# EP4CE75.net
KiCad netlist of a schematic drawn in Altium Designer
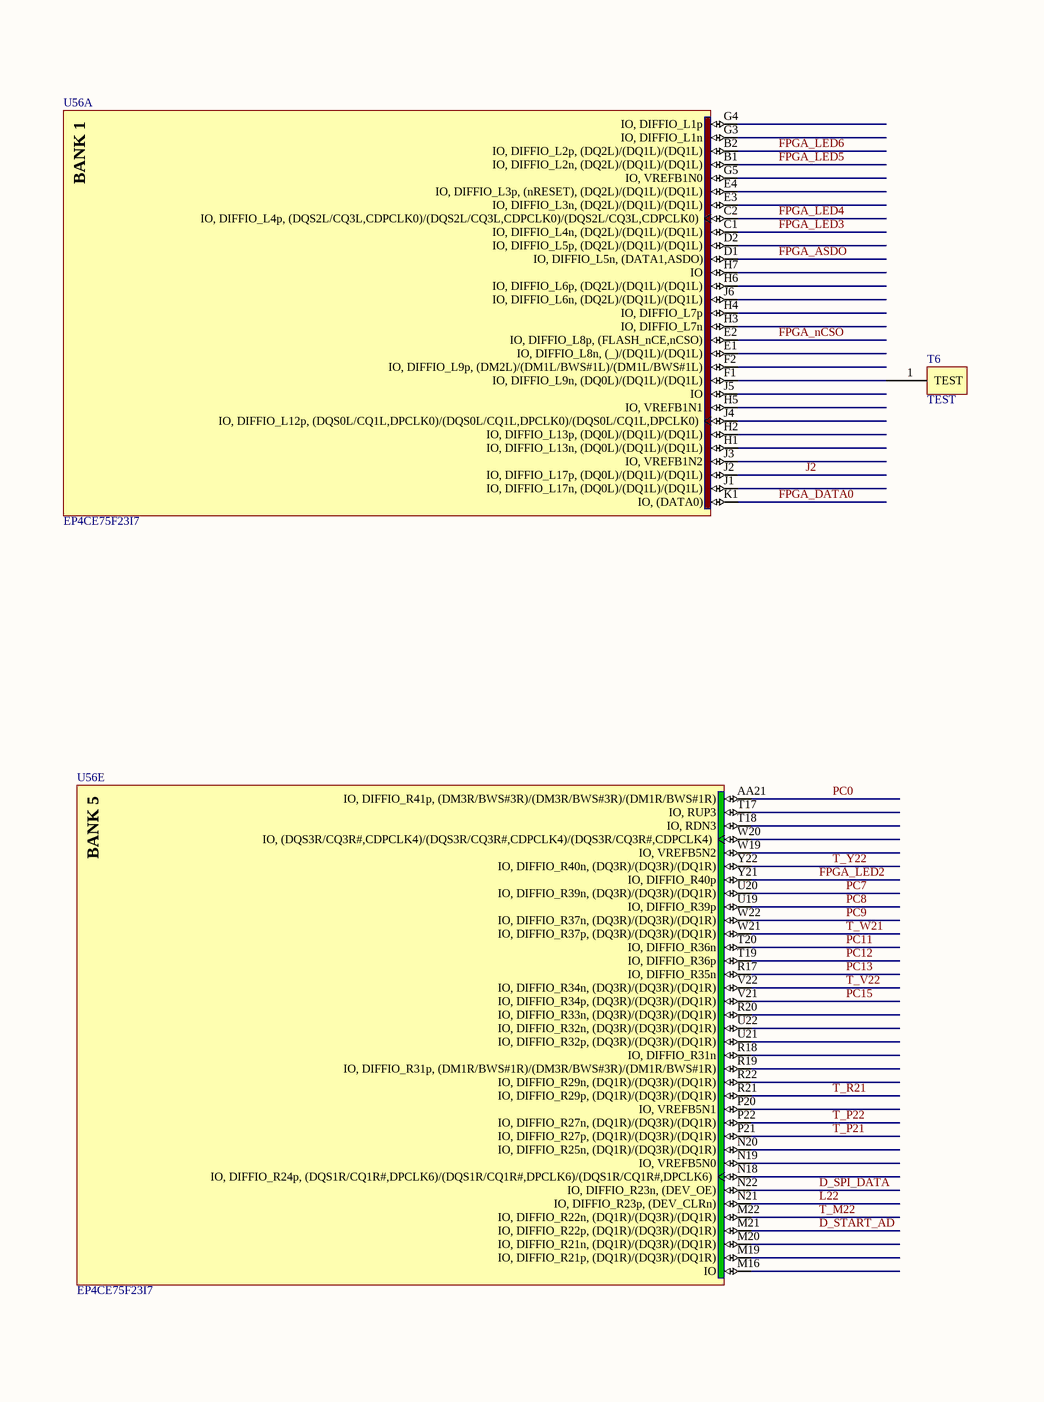
[diagram p0: EP4CE75.SchDoc, top left]
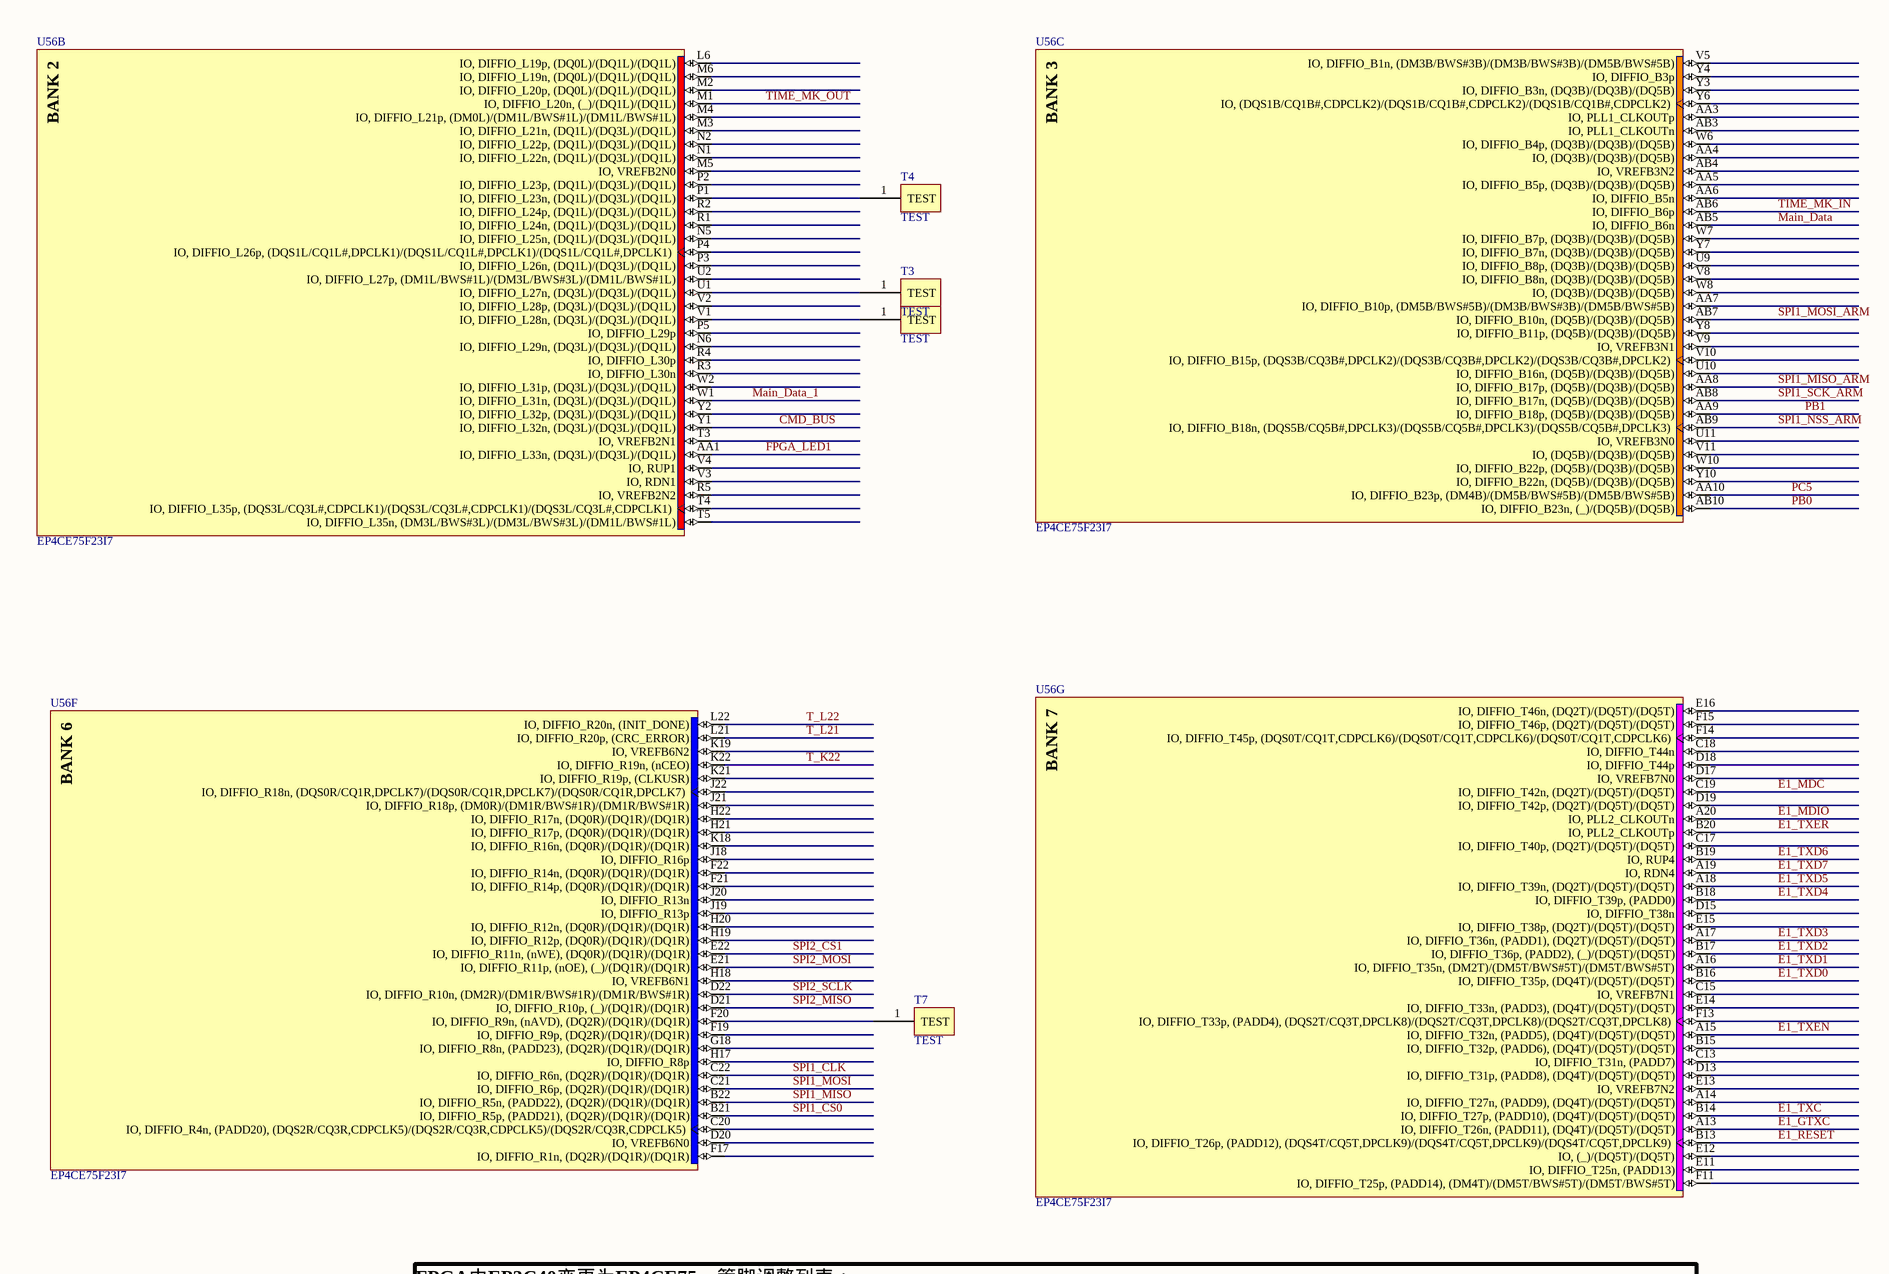
[diagram p1: EP4CE75.SchDoc, top middle]
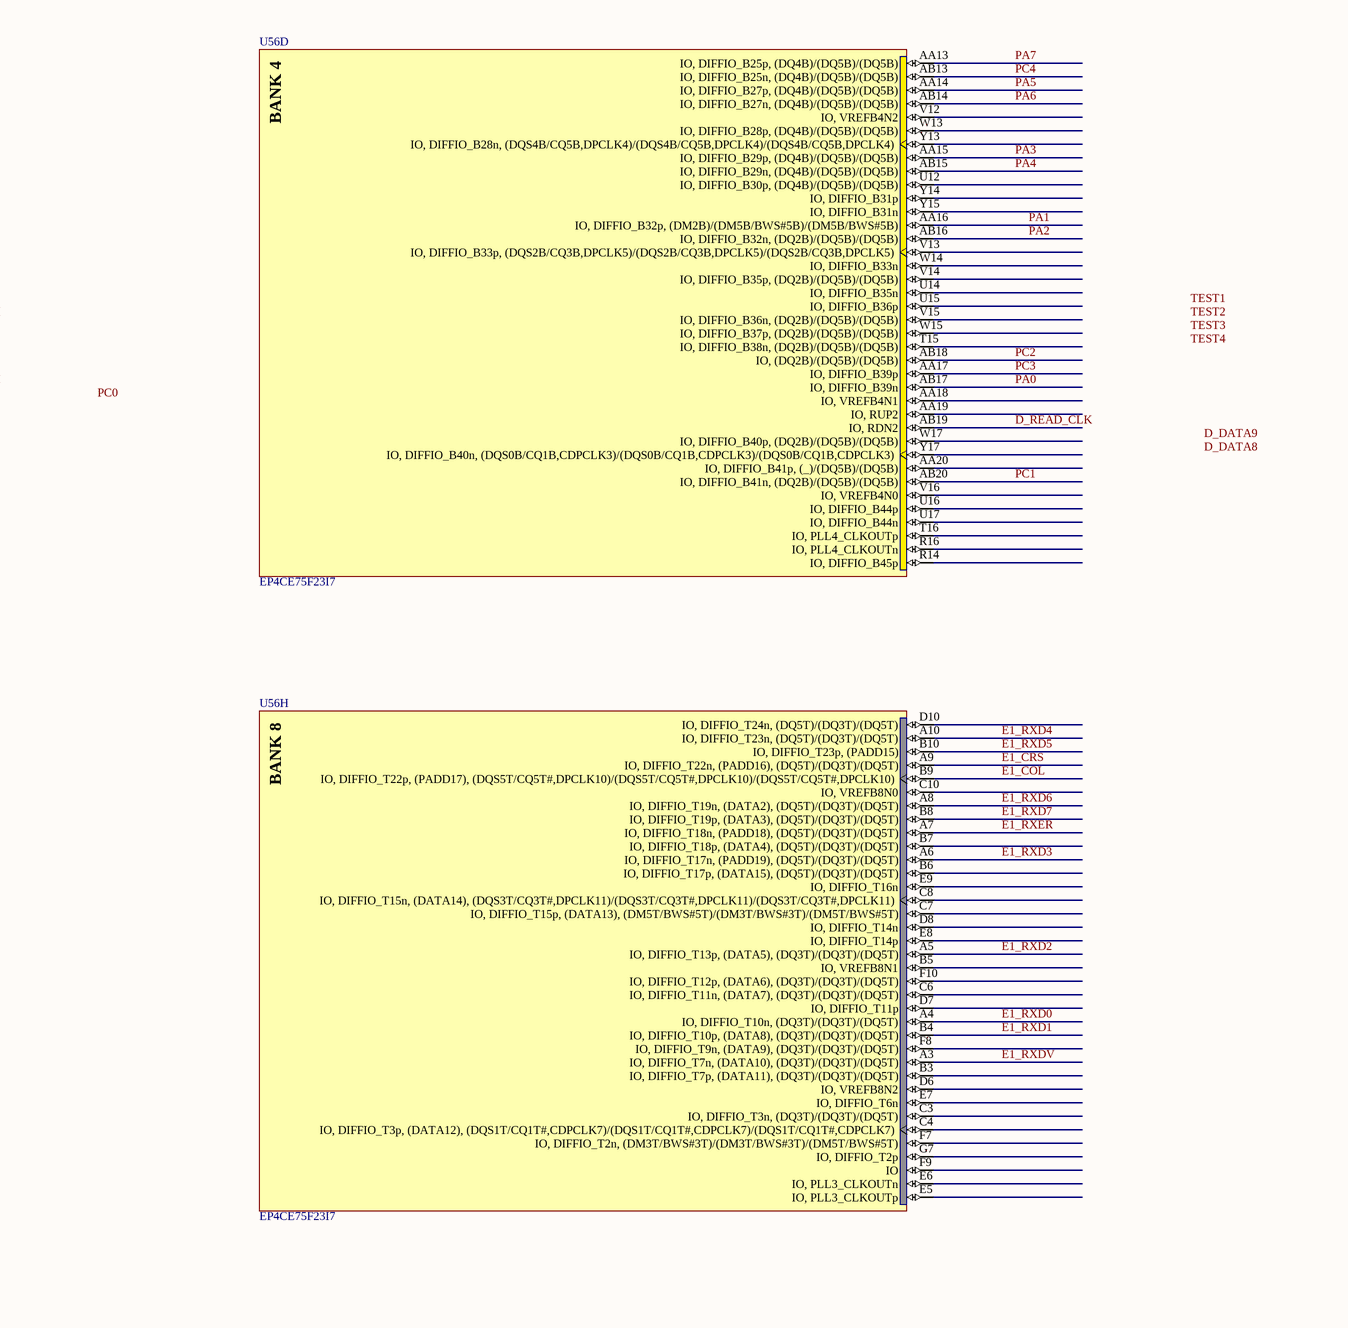
[diagram p2: EP4CE75.SchDoc, top right]
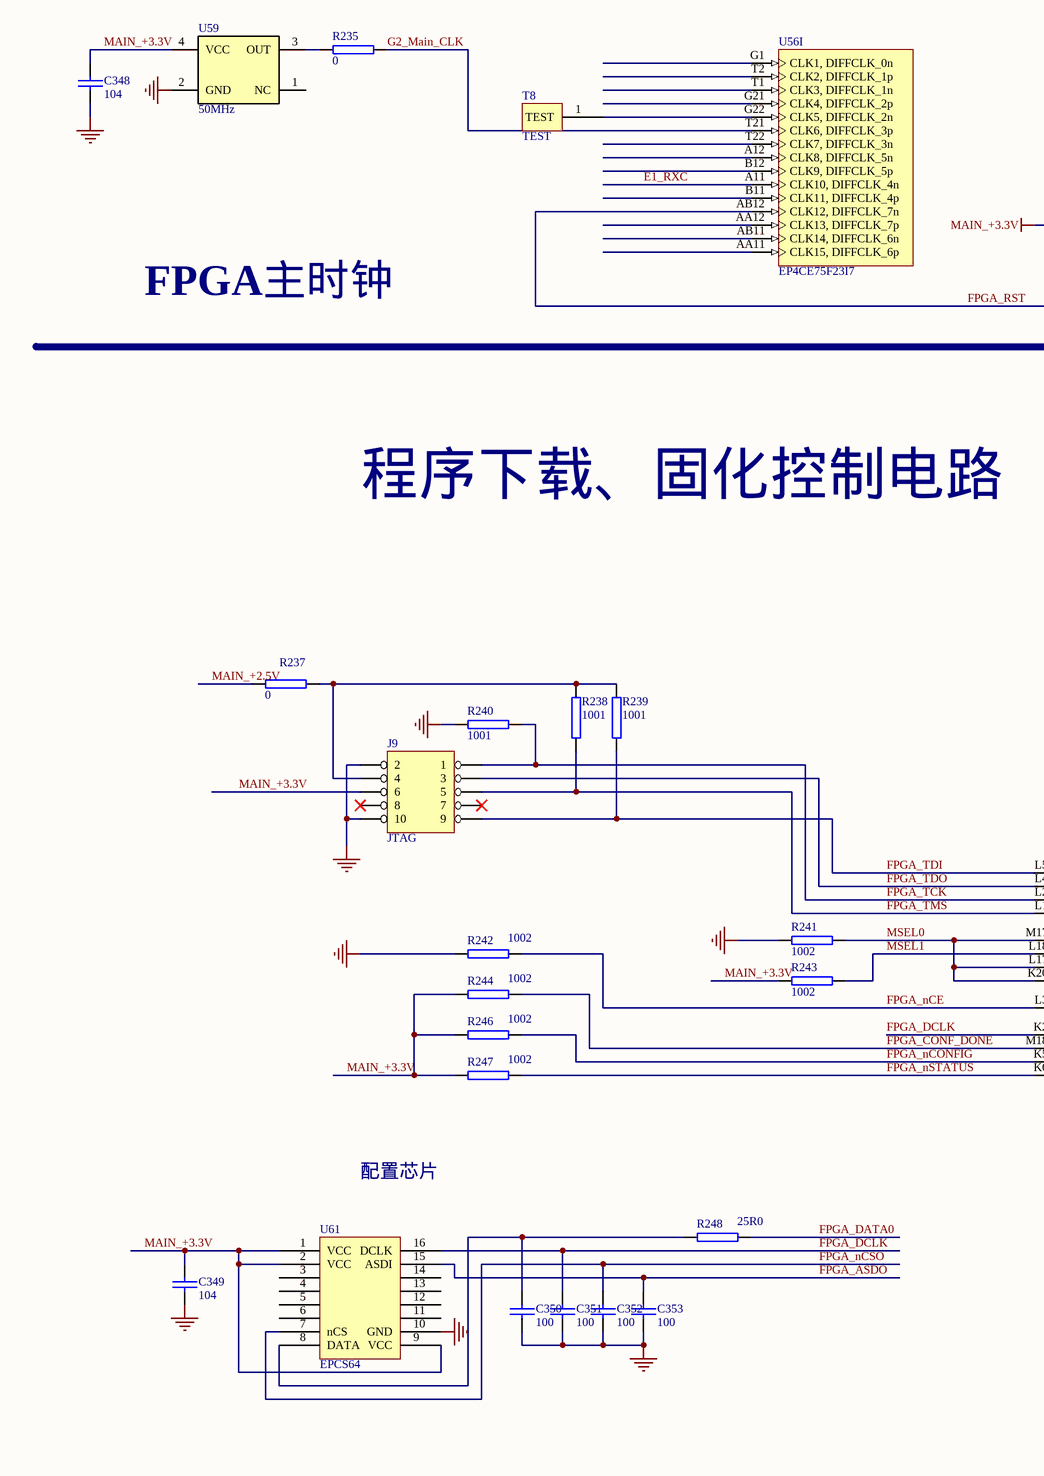
[diagram p3: EP4CE75.SchDoc, bottom left]
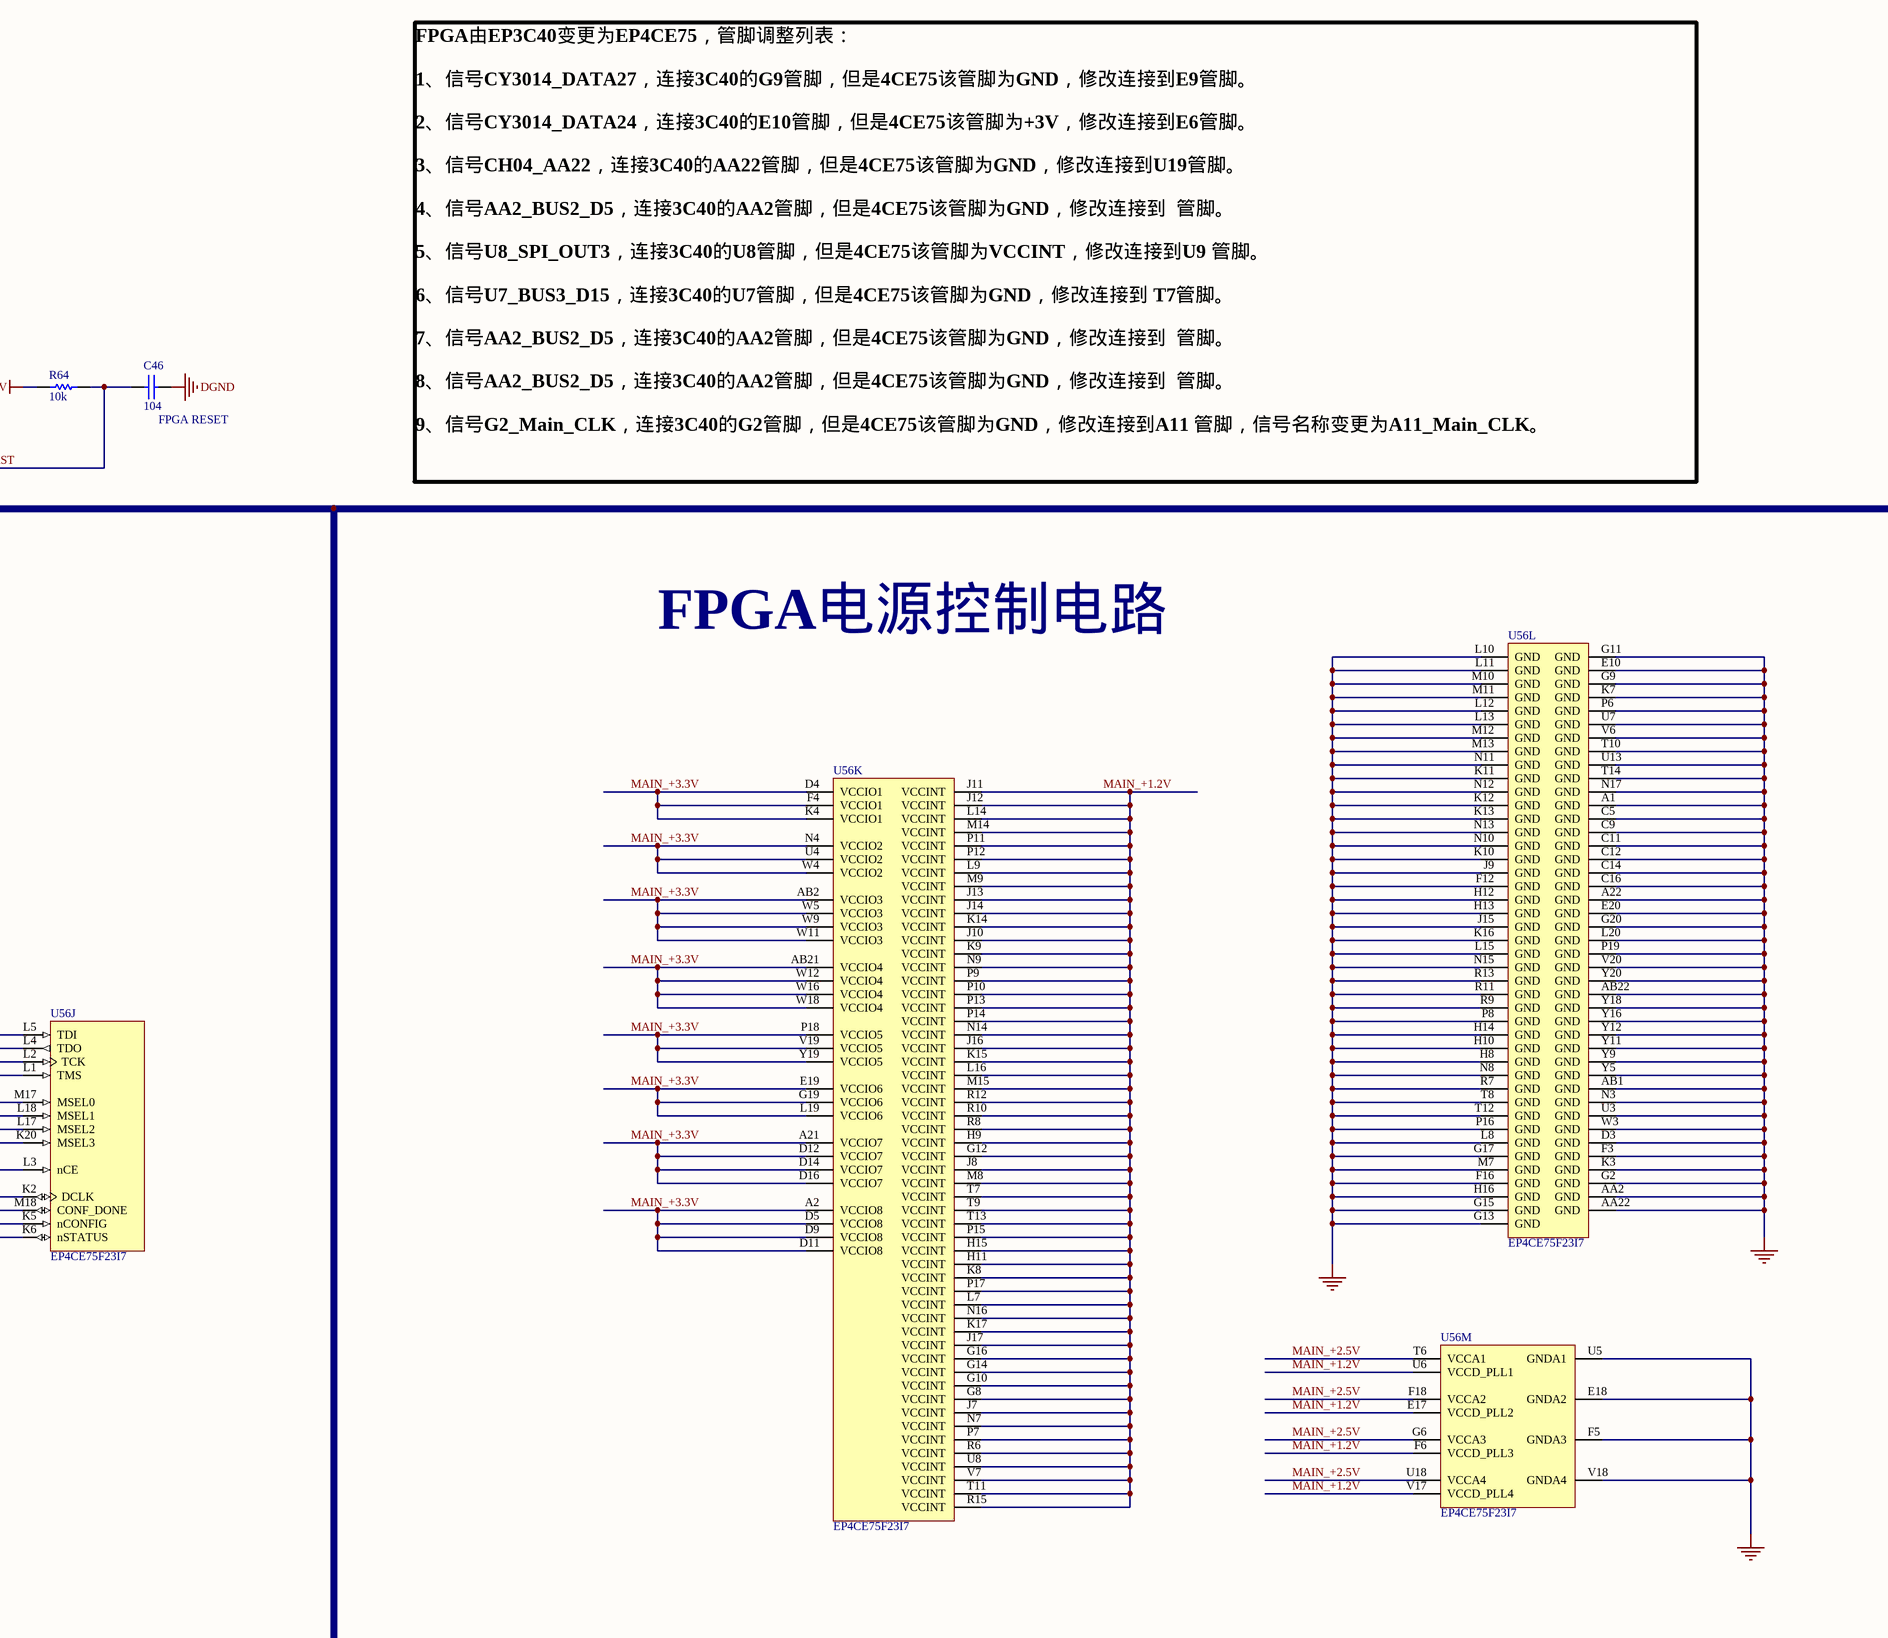
[diagram p4: EP4CE75.SchDoc, bottom middle]
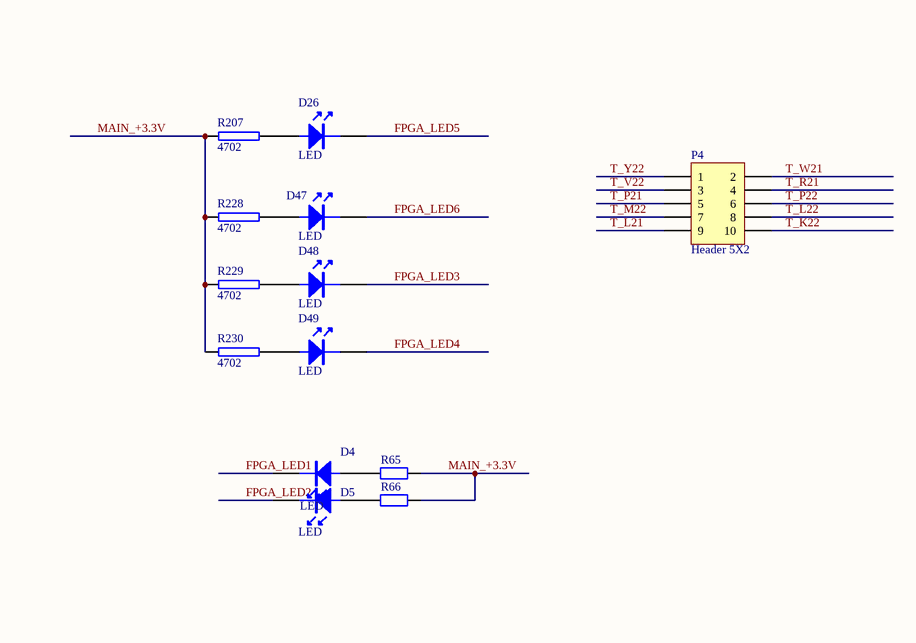
[diagram p5: EP4CE75.SchDoc, bottom right]

(export (version "E")
  (design (tool "Eeschema 10.0.6"))
  (components
    (comp (ref "C46")
      (value "104")
      (footprint "0805C")
      (description "Capacitor")
      (libsource (lib "*") (part "CAP"))
    )
    (comp (ref "C348")
      (value "104")
      (footprint "0805C")
      (description "Capacitor")
      (libsource (lib "") (part "CAP_1"))
    )
    (comp (ref "C349") (value "104") (footprint "0805C") (libsource (lib "*") (part "C")))
    (comp (ref "C350") (value "100") (footprint "0805C") (libsource (lib "*") (part "C")))
    (comp (ref "C351") (value "100") (footprint "0805C") (libsource (lib "*") (part "C")))
    (comp (ref "C352") (value "100") (footprint "0805C") (libsource (lib "*") (part "C")))
    (comp (ref "C353") (value "100") (footprint "0805C") (libsource (lib "*") (part "C")))
    (comp (ref "D4") (value "LED") (footprint "0805_LED") (libsource (lib "*") (part "LED")))
    (comp (ref "D5") (value "LED") (footprint "0805_LED") (libsource (lib "*") (part "LED")))
    (comp (ref "D26") (value "LED") (footprint "0805_LED") (libsource (lib "*") (part "LED")))
    (comp (ref "D47") (value "LED") (footprint "0805_LED") (libsource (lib "*") (part "LED")))
    (comp (ref "D48") (value "LED") (footprint "0805_LED") (libsource (lib "*") (part "LED")))
    (comp (ref "D49") (value "LED") (footprint "0805_LED") (libsource (lib "*") (part "LED")))
    (comp (ref "J9") (value "JTAG") (footprint "IDC10") (libsource (lib "*") (part "HEADER 5X2")))
    (comp (ref "P4")
      (value "Header 5X2")
      (footprint "HDR2X5")
      (description "Header, 5-Pin, Dual row")
      (fields (field (name "PUBLISHER") "Altium Limited"))
      (libsource (lib "Miscellaneous Connectors") (part "Header 5X2"))
    )
    (comp (ref "R64")
      (value "10k")
      (footprint "0805R")
      (description "Resistor")
      (fields (field (name "PUBLISHER") "*"))
      (libsource (lib "*") (part "res1"))
    )
    (comp (ref "R65")
      (value "4701")
      (footprint "0805R")
      (description "Resistor")
      (fields (field (name "PUBLISHER") "Altium Limited"))
      (libsource (lib "Miscellaneous Devices") (part "Res2"))
    )
    (comp (ref "R66")
      (value "4701")
      (footprint "0805R")
      (description "Resistor")
      (fields (field (name "PUBLISHER") "Altium Limited"))
      (libsource (lib "Miscellaneous Devices") (part "Res2"))
    )
    (comp (ref "R207") (value "4702") (footprint "0805R") (libsource (lib "*") (part "RES2")))
    (comp (ref "R228") (value "4702") (footprint "0805R") (libsource (lib "*") (part "RES2")))
    (comp (ref "R229") (value "4702") (footprint "0805R") (libsource (lib "*") (part "RES2")))
    (comp (ref "R230") (value "4702") (footprint "0805R") (libsource (lib "*") (part "RES2")))
    (comp (ref "R235") (value "0") (footprint "0805R") (libsource (lib "*") (part "RES2")))
    (comp (ref "R237") (value "0") (footprint "0805R") (libsource (lib "*") (part "RES2")))
    (comp (ref "R238") (value "1001") (footprint "0805R") (libsource (lib "*") (part "RES2")))
    (comp (ref "R239") (value "1001") (footprint "0805R") (libsource (lib "*") (part "RES2")))
    (comp (ref "R240") (value "1001") (footprint "0805R") (libsource (lib "*") (part "RES2")))
    (comp (ref "R241") (value "1002") (footprint "0805R") (libsource (lib "*") (part "RES2")))
    (comp (ref "R242") (value "1002") (footprint "0402") (libsource (lib "*") (part "RES2")))
    (comp (ref "R243") (value "1002") (footprint "0805R") (libsource (lib "*") (part "RES2")))
    (comp (ref "R244") (value "1002") (footprint "0402") (libsource (lib "*") (part "RES2")))
    (comp (ref "R246") (value "1002") (footprint "0402") (libsource (lib "*") (part "RES2")))
    (comp (ref "R247") (value "1002") (footprint "0402") (libsource (lib "*") (part "RES2")))
    (comp (ref "R248") (value "25R0") (footprint "0805R") (libsource (lib "*") (part "RES2")))
    (comp (ref "T3") (value "TEST") (footprint "TEST_MINI") (libsource (lib "") (part "TEST_1")))
    (comp (ref "T4") (value "TEST") (footprint "TEST_MINI") (libsource (lib "") (part "TEST_1")))
    (comp (ref "T5") (value "TEST") (footprint "TEST_MINI") (libsource (lib "") (part "TEST_1")))
    (comp (ref "T6") (value "TEST") (footprint "TEST_MINI") (libsource (lib "") (part "TEST_1")))
    (comp (ref "T7") (value "TEST") (footprint "TEST_MINI") (libsource (lib "") (part "TEST_1")))
    (comp (ref "T8") (value "TEST") (footprint "TEST_MINI") (libsource (lib "Schlib1") (part "TEST")))
    (comp (ref "U56")
      (value "EP4CE75F23I7")
      (footprint "FBGA484-3")
      (fields (field (name "PUBLISHER") "Altium Limited"))
      (libsource (lib "Altera Cyclone IV E") (part "EP4CE75F23I7"))
    )
    (comp (ref "U59") (value "50MHz") (footprint "CLOCK4") (libsource (lib "*") (part "OSC")))
    (comp (ref "U61")
      (value "EPCS64")
      (footprint "EPCS64_SOIC16")
      (libsource (lib "USB30_Project") (part "EPCS64"))
    )
  )
  (nets
    (net (code "1") (name "/CMD_BUS") (class "Default")
      (node (ref "U56") (pin "Y1") (pinfunction "IO,_DIFFIO_L32n,_(DQ3L)/(DQ3L)/(DQ1L)_Y1") (pintype "bidirectional"))
    )
    (net (code "4") (name "/D_READ_CLK") (class "Default")
      (node (ref "U56") (pin "AB19") (pinfunction "IO,_RDN2_AB19") (pintype "bidirectional"))
    )
    (net (code "5") (name "/D_SPI_DATA") (class "Default")
      (node (ref "U56") (pin "N22") (pinfunction "IO,_DIFFIO_R23n,_(DEV_OE)_N22") (pintype "bidirectional"))
    )
    (net (code "6") (name "/D_START_AD") (class "Default")
      (node (ref "U56") (pin "M21") (pinfunction "IO,_DIFFIO_R22p,_(DQ1R)/(DQ3R)/(DQ1R)_M21") (pintype "bidirectional"))
    )
    (net (code "7") (name "/E1_COL") (class "Default")
      (node (ref "U56") (pin "B9") (pinfunction "IO,_DIFFIO_T22p,_(PADD17),_(DQS5T/CQ5T#,DPCLK10)/(DQS5T/CQ5T#,DPCLK10)/(DQS5T/CQ5T#,DPCLK10)_B9") (pintype "bidirectional"))
    )
    (net (code "8") (name "/E1_CRS") (class "Default")
      (node (ref "U56") (pin "A9") (pinfunction "IO,_DIFFIO_T22n,_(PADD16),_(DQ5T)/(DQ3T)/(DQ5T)_A9") (pintype "bidirectional"))
    )
    (net (code "9") (name "/E1_GTXC") (class "Default")
      (node (ref "U56") (pin "A13") (pinfunction "IO,_DIFFIO_T26n,_(PADD11),_(DQ4T)/(DQ5T)/(DQ5T)_A13") (pintype "bidirectional"))
    )
    (net (code "10") (name "/E1_MDC") (class "Default")
      (node (ref "U56") (pin "C19") (pinfunction "IO,_DIFFIO_T42n,_(DQ2T)/(DQ5T)/(DQ5T)_C19") (pintype "bidirectional"))
    )
    (net (code "11") (name "/E1_MDIO") (class "Default")
      (node (ref "U56") (pin "A20") (pinfunction "IO,_PLL2_CLKOUTn_A20") (pintype "bidirectional"))
    )
    (net (code "12") (name "/E1_RESET") (class "Default")
      (node (ref "U56") (pin "B13") (pinfunction "IO,_DIFFIO_T26p,_(PADD12),_(DQS4T/CQ5T,DPCLK9)/(DQS4T/CQ5T,DPCLK9)/(DQS4T/CQ5T,DPCLK9)_B13") (pintype "bidirectional"))
    )
    (net (code "13") (name "/E1_RXC") (class "Default")
      (node (ref "U56") (pin "A11") (pinfunction "CLK10,_DIFFCLK_4n_A11") (pintype "input"))
    )
    (net (code "14") (name "/E1_RXD0") (class "Default")
      (node (ref "U56") (pin "A4") (pinfunction "IO,_DIFFIO_T10n,_(DQ3T)/(DQ3T)/(DQ5T)_A4") (pintype "bidirectional"))
    )
    (net (code "15") (name "/E1_RXD1") (class "Default")
      (node (ref "U56") (pin "B4") (pinfunction "IO,_DIFFIO_T10p,_(DATA8),_(DQ3T)/(DQ3T)/(DQ5T)_B4") (pintype "bidirectional"))
    )
    (net (code "16") (name "/E1_RXD2") (class "Default")
      (node (ref "U56") (pin "A5") (pinfunction "IO,_DIFFIO_T13p,_(DATA5),_(DQ3T)/(DQ3T)/(DQ5T)_A5") (pintype "bidirectional"))
    )
    (net (code "17") (name "/E1_RXD3") (class "Default")
      (node (ref "U56") (pin "A6") (pinfunction "IO,_DIFFIO_T17n,_(PADD19),_(DQ5T)/(DQ3T)/(DQ5T)_A6") (pintype "bidirectional"))
    )
    (net (code "18") (name "/E1_RXD4") (class "Default")
      (node (ref "U56") (pin "A10") (pinfunction "IO,_DIFFIO_T23n,_(DQ5T)/(DQ3T)/(DQ5T)_A10") (pintype "bidirectional"))
    )
    (net (code "19") (name "/E1_RXD5") (class "Default")
      (node (ref "U56") (pin "B10") (pinfunction "IO,_DIFFIO_T23p,_(PADD15)_B10") (pintype "bidirectional"))
    )
    (net (code "20") (name "/E1_RXD6") (class "Default")
      (node (ref "U56") (pin "A8") (pinfunction "IO,_DIFFIO_T19n,_(DATA2),_(DQ5T)/(DQ3T)/(DQ5T)_A8") (pintype "bidirectional"))
    )
    (net (code "21") (name "/E1_RXD7") (class "Default")
      (node (ref "U56") (pin "B8") (pinfunction "IO,_DIFFIO_T19p,_(DATA3),_(DQ5T)/(DQ3T)/(DQ5T)_B8") (pintype "bidirectional"))
    )
    (net (code "22") (name "/E1_RXDV") (class "Default")
      (node (ref "U56") (pin "A3") (pinfunction "IO,_DIFFIO_T7n,_(DATA10),_(DQ3T)/(DQ3T)/(DQ5T)_A3") (pintype "bidirectional"))
    )
    (net (code "23") (name "/E1_RXER") (class "Default")
      (node (ref "U56") (pin "A7") (pinfunction "IO,_DIFFIO_T18n,_(PADD18),_(DQ5T)/(DQ3T)/(DQ5T)_A7") (pintype "bidirectional"))
    )
    (net (code "24") (name "/E1_TXC") (class "Default")
      (node (ref "U56") (pin "B14") (pinfunction "IO,_DIFFIO_T27p,_(PADD10),_(DQ4T)/(DQ5T)/(DQ5T)_B14") (pintype "bidirectional"))
    )
    (net (code "25") (name "/E1_TXD0") (class "Default")
      (node (ref "U56") (pin "B16") (pinfunction "IO,_DIFFIO_T35p,_(DQ4T)/(DQ5T)/(DQ5T)_B16") (pintype "bidirectional"))
    )
    (net (code "26") (name "/E1_TXD1") (class "Default")
      (node (ref "U56") (pin "A16") (pinfunction "IO,_DIFFIO_T35n,_(DM2T)/(DM5T/BWS#5T)/(DM5T/BWS#5T)_A16") (pintype "bidirectional"))
    )
    (net (code "27") (name "/E1_TXD2") (class "Default")
      (node (ref "U56") (pin "B17") (pinfunction "IO,_DIFFIO_T36p,_(PADD2),_(_)/(DQ5T)/(DQ5T)_B17") (pintype "bidirectional"))
    )
    (net (code "28") (name "/E1_TXD3") (class "Default")
      (node (ref "U56") (pin "A17") (pinfunction "IO,_DIFFIO_T36n,_(PADD1),_(DQ2T)/(DQ5T)/(DQ5T)_A17") (pintype "bidirectional"))
    )
    (net (code "29") (name "/E1_TXD4") (class "Default")
      (node (ref "U56") (pin "B18") (pinfunction "IO,_DIFFIO_T39p,_(PADD0)_B18") (pintype "bidirectional"))
    )
    (net (code "30") (name "/E1_TXD5") (class "Default")
      (node (ref "U56") (pin "A18") (pinfunction "IO,_DIFFIO_T39n,_(DQ2T)/(DQ5T)/(DQ5T)_A18") (pintype "bidirectional"))
    )
    (net (code "31") (name "/E1_TXD6") (class "Default")
      (node (ref "U56") (pin "B19") (pinfunction "IO,_RUP4_B19") (pintype "bidirectional"))
    )
    (net (code "32") (name "/E1_TXD7") (class "Default")
      (node (ref "U56") (pin "A19") (pinfunction "IO,_RDN4_A19") (pintype "bidirectional"))
    )
    (net (code "33") (name "/E1_TXEN") (class "Default")
      (node (ref "U56") (pin "A15") (pinfunction "IO,_DIFFIO_T32n,_(PADD5),_(DQ4T)/(DQ5T)/(DQ5T)_A15") (pintype "bidirectional"))
    )
    (net (code "34") (name "/E1_TXER") (class "Default")
      (node (ref "U56") (pin "B20") (pinfunction "IO,_PLL2_CLKOUTp_B20") (pintype "bidirectional"))
    )
    (net (code "35") (name "/FPGA_ASDO") (class "Default")
      (node (ref "C353") (pin "2") (pintype "passive"))
      (node (ref "U56") (pin "D1") (pinfunction "IO,_DIFFIO_L5n,_(DATA1,ASDO)_D1") (pintype "bidirectional"))
      (node (ref "U61") (pin "15") (pinfunction "ASDI_15") (pintype "passive"))
    )
    (net (code "36") (name "/FPGA_CONF_DONE") (class "Default")
      (node (ref "R244") (pin "2") (pinfunction "2_2") (pintype "passive"))
      (node (ref "U56") (pin "M18") (pinfunction "CONF_DONE_M18") (pintype "bidirectional"))
    )
    (net (code "37") (name "/FPGA_DATA0") (class "Default")
      (node (ref "R248") (pin "1") (pinfunction "1_1") (pintype "passive"))
      (node (ref "U56") (pin "K1") (pinfunction "IO,_(DATA0)_K1") (pintype "bidirectional"))
    )
    (net (code "38") (name "/FPGA_DCLK") (class "Default")
      (node (ref "C351") (pin "2") (pintype "passive"))
      (node (ref "U56") (pin "K2") (pinfunction "DCLK_K2") (pintype "bidirectional"))
      (node (ref "U61") (pin "16") (pinfunction "DCLK_16") (pintype "passive"))
    )
    (net (code "39") (name "/FPGA_LED1") (class "Default")
      (node (ref "D4") (pin "2") (pinfunction "K_2") (pintype "passive"))
      (node (ref "U56") (pin "AA1") (pinfunction "IO,_DIFFIO_L33n,_(DQ3L)/(DQ3L)/(DQ1L)_AA1") (pintype "bidirectional"))
    )
    (net (code "40") (name "/FPGA_LED2") (class "Default")
      (node (ref "D5") (pin "2") (pinfunction "K_2") (pintype "passive"))
      (node (ref "U56") (pin "Y21") (pinfunction "IO,_DIFFIO_R40p_Y21") (pintype "bidirectional"))
    )
    (net (code "41") (name "/FPGA_LED3") (class "Default")
      (node (ref "D48") (pin "2") (pinfunction "K_2") (pintype "passive"))
      (node (ref "U56") (pin "C1") (pinfunction "IO,_DIFFIO_L4n,_(DQ2L)/(DQ1L)/(DQ1L)_C1") (pintype "bidirectional"))
    )
    (net (code "42") (name "/FPGA_LED4") (class "Default")
      (node (ref "D49") (pin "2") (pinfunction "K_2") (pintype "passive"))
      (node (ref "U56") (pin "C2") (pinfunction "IO,_DIFFIO_L4p,_(DQS2L/CQ3L,CDPCLK0)/(DQS2L/CQ3L,CDPCLK0)/(DQS2L/CQ3L,CDPCLK0)_C2") (pintype "bidirectional"))
    )
    (net (code "43") (name "/FPGA_LED5") (class "Default")
      (node (ref "D26") (pin "2") (pinfunction "K_2") (pintype "passive"))
      (node (ref "U56") (pin "B1") (pinfunction "IO,_DIFFIO_L2n,_(DQ2L)/(DQ1L)/(DQ1L)_B1") (pintype "bidirectional"))
    )
    (net (code "44") (name "/FPGA_LED6") (class "Default")
      (node (ref "D47") (pin "2") (pinfunction "K_2") (pintype "passive"))
      (node (ref "U56") (pin "B2") (pinfunction "IO,_DIFFIO_L2p,_(DQ2L)/(DQ1L)/(DQ1L)_B2") (pintype "bidirectional"))
    )
    (net (code "45") (name "/FPGA_RST") (class "Default")
      (node (ref "C46") (pin "1") (pinfunction "1_1") (pintype "passive"))
      (node (ref "R64") (pin "1") (pinfunction "1_1") (pintype "passive"))
      (node (ref "U56") (pin "AB12") (pinfunction "CLK12,_DIFFCLK_7n_AB12") (pintype "input"))
    )
    (net (code "46") (name "/FPGA_TCK") (class "Default")
      (node (ref "J9") (pin "1") (pinfunction "1_1") (pintype "passive"))
      (node (ref "R240") (pin "2") (pinfunction "2_2") (pintype "passive"))
      (node (ref "U56") (pin "L2") (pinfunction "TCK_L2") (pintype "input"))
    )
    (net (code "47") (name "/FPGA_TDI") (class "Default")
      (node (ref "J9") (pin "9") (pinfunction "9_9") (pintype "passive"))
      (node (ref "R239") (pin "1") (pinfunction "1_1") (pintype "passive"))
      (node (ref "U56") (pin "L5") (pinfunction "TDI_L5") (pintype "input"))
    )
    (net (code "48") (name "/FPGA_TDO") (class "Default")
      (node (ref "J9") (pin "3") (pinfunction "3_3") (pintype "passive"))
      (node (ref "U56") (pin "L4") (pinfunction "TDO_L4") (pintype "output"))
    )
    (net (code "49") (name "/FPGA_TMS") (class "Default")
      (node (ref "J9") (pin "5") (pinfunction "5_5") (pintype "passive"))
      (node (ref "R238") (pin "1") (pinfunction "1_1") (pintype "passive"))
      (node (ref "U56") (pin "L1") (pinfunction "TMS_L1") (pintype "input"))
    )
    (net (code "50") (name "/FPGA_nCE") (class "Default")
      (node (ref "R242") (pin "1") (pinfunction "1_1") (pintype "passive"))
      (node (ref "U56") (pin "L3") (pinfunction "nCE_L3") (pintype "input"))
    )
    (net (code "51") (name "/FPGA_nCONFIG") (class "Default")
      (node (ref "R246") (pin "1") (pinfunction "1_1") (pintype "passive"))
      (node (ref "U56") (pin "K5") (pinfunction "nCONFIG_K5") (pintype "input"))
    )
    (net (code "52") (name "/FPGA_nCSO") (class "Default")
      (node (ref "C352") (pin "2") (pintype "passive"))
      (node (ref "U56") (pin "E2") (pinfunction "IO,_DIFFIO_L8p,_(FLASH_nCE,nCSO)_E2") (pintype "bidirectional"))
      (node (ref "U61") (pin "7") (pinfunction "nCS_7") (pintype "passive"))
    )
    (net (code "53") (name "/FPGA_nSTATUS") (class "Default")
      (node (ref "R247") (pin "1") (pinfunction "1_1") (pintype "passive"))
      (node (ref "U56") (pin "K6") (pinfunction "nSTATUS_K6") (pintype "bidirectional"))
    )
    (net (code "54") (name "/G2_Main_CLK") (class "Default")
      (node (ref "R235") (pin "2") (pinfunction "2_2") (pintype "passive"))
      (node (ref "U56") (pin "T21") (pinfunction "CLK6,_DIFFCLK_3p_T21") (pintype "input"))
    )
    (net (code "55") (name "/J2") (class "Default")
      (node (ref "U56") (pin "J2") (pinfunction "IO,_DIFFIO_L17p,_(DQ0L)/(DQ1L)/(DQ1L)_J2") (pintype "bidirectional"))
    )
    (net (code "56") (name "/L22") (class "Default")
      (node (ref "U56") (pin "N21") (pinfunction "IO,_DIFFIO_R23p,_(DEV_CLRn)_N21") (pintype "bidirectional"))
    )
    (net (code "57") (name "/MAIN_+1.2V") (class "Default")
      (node (ref "U56") (pin "E17") (pinfunction "VCCD_PLL2_E17") (pintype "power_in"))
      (node (ref "U56") (pin "F6") (pinfunction "VCCD_PLL3_F6") (pintype "power_in"))
      (node (ref "U56") (pin "G10") (pinfunction "VCCINT_G10") (pintype "power_in"))
      (node (ref "U56") (pin "G12") (pinfunction "VCCINT_G12") (pintype "power_in"))
      (node (ref "U56") (pin "G14") (pinfunction "VCCINT_G14") (pintype "power_in"))
      (node (ref "U56") (pin "G16") (pinfunction "VCCINT_G16") (pintype "power_in"))
      (node (ref "U56") (pin "G8") (pinfunction "VCCINT_G8") (pintype "power_in"))
      (node (ref "U56") (pin "H11") (pinfunction "VCCINT_H11") (pintype "power_in"))
      (node (ref "U56") (pin "H15") (pinfunction "VCCINT_H15") (pintype "power_in"))
      (node (ref "U56") (pin "H9") (pinfunction "VCCINT_H9") (pintype "power_in"))
      (node (ref "U56") (pin "J10") (pinfunction "VCCINT_J10") (pintype "power_in"))
      (node (ref "U56") (pin "J11") (pinfunction "VCCINT_J11") (pintype "power_in"))
      (node (ref "U56") (pin "J12") (pinfunction "VCCINT_J12") (pintype "power_in"))
      (node (ref "U56") (pin "J13") (pinfunction "VCCINT_J13") (pintype "power_in"))
      (node (ref "U56") (pin "J14") (pinfunction "VCCINT_J14") (pintype "power_in"))
      (node (ref "U56") (pin "J16") (pinfunction "VCCINT_J16") (pintype "power_in"))
      (node (ref "U56") (pin "J17") (pinfunction "VCCINT_J17") (pintype "power_in"))
      (node (ref "U56") (pin "J7") (pinfunction "VCCINT_J7") (pintype "power_in"))
      (node (ref "U56") (pin "J8") (pinfunction "VCCINT_J8") (pintype "power_in"))
      (node (ref "U56") (pin "K14") (pinfunction "VCCINT_K14") (pintype "power_in"))
      (node (ref "U56") (pin "K15") (pinfunction "VCCINT_K15") (pintype "power_in"))
      (node (ref "U56") (pin "K17") (pinfunction "VCCINT_K17") (pintype "power_in"))
      (node (ref "U56") (pin "K8") (pinfunction "VCCINT_K8") (pintype "power_in"))
      (node (ref "U56") (pin "K9") (pinfunction "VCCINT_K9") (pintype "power_in"))
      (node (ref "U56") (pin "L14") (pinfunction "VCCINT_L14") (pintype "power_in"))
      (node (ref "U56") (pin "L16") (pinfunction "VCCINT_L16") (pintype "power_in"))
      (node (ref "U56") (pin "L7") (pinfunction "VCCINT_L7") (pintype "power_in"))
      (node (ref "U56") (pin "L9") (pinfunction "VCCINT_L9") (pintype "power_in"))
      (node (ref "U56") (pin "M14") (pinfunction "VCCINT_M14") (pintype "power_in"))
      (node (ref "U56") (pin "M15") (pinfunction "VCCINT_M15") (pintype "power_in"))
      (node (ref "U56") (pin "M8") (pinfunction "VCCINT_M8") (pintype "power_in"))
      (node (ref "U56") (pin "M9") (pinfunction "VCCINT_M9") (pintype "power_in"))
      (node (ref "U56") (pin "N14") (pinfunction "VCCINT_N14") (pintype "power_in"))
      (node (ref "U56") (pin "N16") (pinfunction "VCCINT_N16") (pintype "power_in"))
      (node (ref "U56") (pin "N7") (pinfunction "VCCINT_N7") (pintype "power_in"))
      (node (ref "U56") (pin "N9") (pinfunction "VCCINT_N9") (pintype "power_in"))
      (node (ref "U56") (pin "P10") (pinfunction "VCCINT_P10") (pintype "power_in"))
      (node (ref "U56") (pin "P11") (pinfunction "VCCINT_P11") (pintype "power_in"))
      (node (ref "U56") (pin "P12") (pinfunction "VCCINT_P12") (pintype "power_in"))
      (node (ref "U56") (pin "P13") (pinfunction "VCCINT_P13") (pintype "power_in"))
      (node (ref "U56") (pin "P14") (pinfunction "VCCINT_P14") (pintype "power_in"))
      (node (ref "U56") (pin "P15") (pinfunction "VCCINT_P15") (pintype "power_in"))
      (node (ref "U56") (pin "P17") (pinfunction "VCCINT_P17") (pintype "power_in"))
      (node (ref "U56") (pin "P7") (pinfunction "VCCINT_P7") (pintype "power_in"))
      (node (ref "U56") (pin "P9") (pinfunction "VCCINT_P9") (pintype "power_in"))
      (node (ref "U56") (pin "R10") (pinfunction "VCCINT_R10") (pintype "power_in"))
      (node (ref "U56") (pin "R12") (pinfunction "VCCINT_R12") (pintype "power_in"))
      (node (ref "U56") (pin "R15") (pinfunction "VCCINT_R15") (pintype "power_in"))
      (node (ref "U56") (pin "R6") (pinfunction "VCCINT_R6") (pintype "power_in"))
      (node (ref "U56") (pin "R8") (pinfunction "VCCINT_R8") (pintype "power_in"))
      (node (ref "U56") (pin "T11") (pinfunction "VCCINT_T11") (pintype "power_in"))
      (node (ref "U56") (pin "T13") (pinfunction "VCCINT_T13") (pintype "power_in"))
      (node (ref "U56") (pin "T7") (pinfunction "VCCINT_T7") (pintype "power_in"))
      (node (ref "U56") (pin "T9") (pinfunction "VCCINT_T9") (pintype "power_in"))
      (node (ref "U56") (pin "U6") (pinfunction "VCCD_PLL1_U6") (pintype "power_in"))
      (node (ref "U56") (pin "U8") (pinfunction "VCCINT_U8") (pintype "power_in"))
      (node (ref "U56") (pin "V17") (pinfunction "VCCD_PLL4_V17") (pintype "power_in"))
      (node (ref "U56") (pin "V7") (pinfunction "VCCINT_V7") (pintype "power_in"))
    )
    (net (code "58") (name "/MAIN_+2.5V") (class "Default")
      (node (ref "R237") (pin "1") (pinfunction "1_1") (pintype "passive"))
      (node (ref "U56") (pin "F18") (pinfunction "VCCA2_F18") (pintype "power_in"))
      (node (ref "U56") (pin "G6") (pinfunction "VCCA3_G6") (pintype "power_in"))
      (node (ref "U56") (pin "T6") (pinfunction "VCCA1_T6") (pintype "power_in"))
      (node (ref "U56") (pin "U18") (pinfunction "VCCA4_U18") (pintype "power_in"))
    )
    (net (code "59") (name "/MSEL0") (class "Default")
      (node (ref "R241") (pin "2") (pinfunction "2_2") (pintype "passive"))
      (node (ref "U56") (pin "K20") (pinfunction "MSEL3_K20") (pintype "input"))
      (node (ref "U56") (pin "L17") (pinfunction "MSEL2_L17") (pintype "input"))
      (node (ref "U56") (pin "M17") (pinfunction "MSEL0_M17") (pintype "input"))
    )
    (net (code "60") (name "/MSEL1") (class "Default")
      (node (ref "R243") (pin "2") (pinfunction "2_2") (pintype "passive"))
      (node (ref "U56") (pin "L18") (pinfunction "MSEL1_L18") (pintype "input"))
    )
    (net (code "61") (name "/Main_Data") (class "Default")
      (node (ref "U56") (pin "AB5") (pinfunction "IO,_DIFFIO_B6n_AB5") (pintype "bidirectional"))
    )
    (net (code "62") (name "/Main_Data_1") (class "Default")
      (node (ref "U56") (pin "W1") (pinfunction "IO,_DIFFIO_L31n,_(DQ3L)/(DQ3L)/(DQ1L)_W1") (pintype "bidirectional"))
    )
    (net (code "63") (name "/PA0") (class "Default")
      (node (ref "U56") (pin "AB17") (pinfunction "IO,_DIFFIO_B39n_AB17") (pintype "bidirectional"))
    )
    (net (code "64") (name "/PA1") (class "Default")
      (node (ref "U56") (pin "AA16") (pinfunction "IO,_DIFFIO_B32p,_(DM2B)/(DM5B/BWS#5B)/(DM5B/BWS#5B)_AA16") (pintype "bidirectional"))
    )
    (net (code "65") (name "/PA2") (class "Default")
      (node (ref "U56") (pin "AB16") (pinfunction "IO,_DIFFIO_B32n,_(DQ2B)/(DQ5B)/(DQ5B)_AB16") (pintype "bidirectional"))
    )
    (net (code "66") (name "/PA3") (class "Default")
      (node (ref "U56") (pin "AA15") (pinfunction "IO,_DIFFIO_B29p,_(DQ4B)/(DQ5B)/(DQ5B)_AA15") (pintype "bidirectional"))
    )
    (net (code "67") (name "/PA4") (class "Default")
      (node (ref "U56") (pin "AB15") (pinfunction "IO,_DIFFIO_B29n,_(DQ4B)/(DQ5B)/(DQ5B)_AB15") (pintype "bidirectional"))
    )
    (net (code "68") (name "/PA5") (class "Default")
      (node (ref "U56") (pin "AA14") (pinfunction "IO,_DIFFIO_B27p,_(DQ4B)/(DQ5B)/(DQ5B)_AA14") (pintype "bidirectional"))
    )
    (net (code "69") (name "/PA6") (class "Default")
      (node (ref "U56") (pin "AB14") (pinfunction "IO,_DIFFIO_B27n,_(DQ4B)/(DQ5B)/(DQ5B)_AB14") (pintype "bidirectional"))
    )
    (net (code "70") (name "/PA7") (class "Default")
      (node (ref "U56") (pin "AA13") (pinfunction "IO,_DIFFIO_B25p,_(DQ4B)/(DQ5B)/(DQ5B)_AA13") (pintype "bidirectional"))
    )
    (net (code "71") (name "/PB0") (class "Default")
      (node (ref "U56") (pin "AB10") (pinfunction "IO,_DIFFIO_B23n,_(_)/(DQ5B)/(DQ5B)_AB10") (pintype "bidirectional"))
    )
    (net (code "72") (name "/PB1") (class "Default")
      (node (ref "U56") (pin "AA9") (pinfunction "IO,_DIFFIO_B18p,_(DQ5B)/(DQ3B)/(DQ5B)_AA9") (pintype "bidirectional"))
    )
    (net (code "73") (name "/PC0") (class "Default")
      (node (ref "U56") (pin "AA21") (pinfunction "IO,_DIFFIO_R41p,_(DM3R/BWS#3R)/(DM3R/BWS#3R)/(DM1R/BWS#1R)_AA21") (pintype "bidirectional"))
    )
    (net (code "74") (name "/PC1") (class "Default")
      (node (ref "U56") (pin "AB20") (pinfunction "IO,_DIFFIO_B41n,_(DQ2B)/(DQ5B)/(DQ5B)_AB20") (pintype "bidirectional"))
    )
    (net (code "75") (name "/PC2") (class "Default")
      (node (ref "U56") (pin "AB18") (pinfunction "IO,_(DQ2B)/(DQ5B)/(DQ5B)_AB18") (pintype "bidirectional"))
    )
    (net (code "76") (name "/PC3") (class "Default")
      (node (ref "U56") (pin "AA17") (pinfunction "IO,_DIFFIO_B39p_AA17") (pintype "bidirectional"))
    )
    (net (code "77") (name "/PC4") (class "Default")
      (node (ref "U56") (pin "AB13") (pinfunction "IO,_DIFFIO_B25n,_(DQ4B)/(DQ5B)/(DQ5B)_AB13") (pintype "bidirectional"))
    )
    (net (code "78") (name "/PC5") (class "Default")
      (node (ref "U56") (pin "AA10") (pinfunction "IO,_DIFFIO_B23p,_(DM4B)/(DM5B/BWS#5B)/(DM5B/BWS#5B)_AA10") (pintype "bidirectional"))
    )
    (net (code "79") (name "/PC7") (class "Default")
      (node (ref "U56") (pin "U20") (pinfunction "IO,_DIFFIO_R39n,_(DQ3R)/(DQ3R)/(DQ1R)_U20") (pintype "bidirectional"))
    )
    (net (code "80") (name "/PC8") (class "Default")
      (node (ref "U56") (pin "U19") (pinfunction "IO,_DIFFIO_R39p_U19") (pintype "bidirectional"))
    )
    (net (code "81") (name "/PC9") (class "Default")
      (node (ref "U56") (pin "W22") (pinfunction "IO,_DIFFIO_R37n,_(DQ3R)/(DQ3R)/(DQ1R)_W22") (pintype "bidirectional"))
    )
    (net (code "82") (name "/PC11") (class "Default")
      (node (ref "U56") (pin "T20") (pinfunction "IO,_DIFFIO_R36n_T20") (pintype "bidirectional"))
    )
    (net (code "83") (name "/PC12") (class "Default")
      (node (ref "U56") (pin "T19") (pinfunction "IO,_DIFFIO_R36p_T19") (pintype "bidirectional"))
    )
    (net (code "84") (name "/PC13") (class "Default")
      (node (ref "U56") (pin "R17") (pinfunction "IO,_DIFFIO_R35n_R17") (pintype "bidirectional"))
    )
    (net (code "85") (name "/PC15") (class "Default")
      (node (ref "U56") (pin "V21") (pinfunction "IO,_DIFFIO_R34p,_(DQ3R)/(DQ3R)/(DQ1R)_V21") (pintype "bidirectional"))
    )
    (net (code "86") (name "/SPI1_CLK") (class "Default")
      (node (ref "U56") (pin "C22") (pinfunction "IO,_DIFFIO_R6n,_(DQ2R)/(DQ1R)/(DQ1R)_C22") (pintype "bidirectional"))
    )
    (net (code "87") (name "/SPI1_CS0") (class "Default")
      (node (ref "U56") (pin "B21") (pinfunction "IO,_DIFFIO_R5p,_(PADD21),_(DQ2R)/(DQ1R)/(DQ1R)_B21") (pintype "bidirectional"))
    )
    (net (code "88") (name "/SPI1_MISO") (class "Default")
      (node (ref "U56") (pin "B22") (pinfunction "IO,_DIFFIO_R5n,_(PADD22),_(DQ2R)/(DQ1R)/(DQ1R)_B22") (pintype "bidirectional"))
    )
    (net (code "89") (name "/SPI1_MISO_ARM") (class "Default")
      (node (ref "U56") (pin "AA8") (pinfunction "IO,_DIFFIO_B17p,_(DQ5B)/(DQ3B)/(DQ5B)_AA8") (pintype "bidirectional"))
    )
    (net (code "90") (name "/SPI1_MOSI") (class "Default")
      (node (ref "U56") (pin "C21") (pinfunction "IO,_DIFFIO_R6p,_(DQ2R)/(DQ1R)/(DQ1R)_C21") (pintype "bidirectional"))
    )
    (net (code "91") (name "/SPI1_MOSI_ARM") (class "Default")
      (node (ref "U56") (pin "AB7") (pinfunction "IO,_DIFFIO_B10n,_(DQ5B)/(DQ3B)/(DQ5B)_AB7") (pintype "bidirectional"))
    )
    (net (code "92") (name "/SPI1_NSS_ARM") (class "Default")
      (node (ref "U56") (pin "AB9") (pinfunction "IO,_DIFFIO_B18n,_(DQS5B/CQ5B#,DPCLK3)/(DQS5B/CQ5B#,DPCLK3)/(DQS5B/CQ5B#,DPCLK3)_AB9") (pintype "bidirectional"))
    )
    (net (code "93") (name "/SPI1_SCK_ARM") (class "Default")
      (node (ref "U56") (pin "AB8") (pinfunction "IO,_DIFFIO_B17n,_(DQ5B)/(DQ3B)/(DQ5B)_AB8") (pintype "bidirectional"))
    )
    (net (code "94") (name "/SPI2_CS1") (class "Default")
      (node (ref "U56") (pin "E22") (pinfunction "IO,_DIFFIO_R11n,_(nWE),_(DQ0R)/(DQ1R)/(DQ1R)_E22") (pintype "bidirectional"))
    )
    (net (code "95") (name "/SPI2_MISO") (class "Default")
      (node (ref "U56") (pin "D21") (pinfunction "IO,_DIFFIO_R10p,_(_)/(DQ1R)/(DQ1R)_D21") (pintype "bidirectional"))
    )
    (net (code "96") (name "/SPI2_MOSI") (class "Default")
      (node (ref "U56") (pin "E21") (pinfunction "IO,_DIFFIO_R11p,_(nOE),_(_)/(DQ1R)/(DQ1R)_E21") (pintype "bidirectional"))
    )
    (net (code "97") (name "/SPI2_SCLK") (class "Default")
      (node (ref "U56") (pin "D22") (pinfunction "IO,_DIFFIO_R10n,_(DM2R)/(DM1R/BWS#1R)/(DM1R/BWS#1R)_D22") (pintype "bidirectional"))
    )
    (net (code "102") (name "/TIME_MK_IN") (class "Default")
      (node (ref "U56") (pin "AB6") (pinfunction "IO,_DIFFIO_B6p_AB6") (pintype "bidirectional"))
    )
    (net (code "103") (name "/TIME_MK_OUT") (class "Default")
      (node (ref "U56") (pin "M1") (pinfunction "IO,_DIFFIO_L20n,_(_)/(DQ1L)/(DQ1L)_M1") (pintype "bidirectional"))
    )
    (net (code "104") (name "/T_K22") (class "Default")
      (node (ref "P4") (pin "10") (pinfunction "10_10") (pintype "passive"))
      (node (ref "U56") (pin "K22") (pinfunction "IO,_DIFFIO_R19n,_(nCEO)_K22") (pintype "bidirectional"))
    )
    (net (code "105") (name "/T_L21") (class "Default")
      (node (ref "P4") (pin "9") (pinfunction "9_9") (pintype "passive"))
      (node (ref "U56") (pin "L21") (pinfunction "IO,_DIFFIO_R20p,_(CRC_ERROR)_L21") (pintype "bidirectional"))
    )
    (net (code "106") (name "/T_L22") (class "Default")
      (node (ref "P4") (pin "8") (pinfunction "8_8") (pintype "passive"))
      (node (ref "U56") (pin "L22") (pinfunction "IO,_DIFFIO_R20n,_(INIT_DONE)_L22") (pintype "bidirectional"))
    )
    (net (code "107") (name "/T_M22") (class "Default")
      (node (ref "P4") (pin "7") (pinfunction "7_7") (pintype "passive"))
      (node (ref "U56") (pin "M22") (pinfunction "IO,_DIFFIO_R22n,_(DQ1R)/(DQ3R)/(DQ1R)_M22") (pintype "bidirectional"))
    )
    (net (code "108") (name "/T_P21") (class "Default")
      (node (ref "P4") (pin "5") (pinfunction "5_5") (pintype "passive"))
      (node (ref "U56") (pin "P21") (pinfunction "IO,_DIFFIO_R27p,_(DQ1R)/(DQ3R)/(DQ1R)_P21") (pintype "bidirectional"))
    )
    (net (code "109") (name "/T_P22") (class "Default")
      (node (ref "P4") (pin "6") (pinfunction "6_6") (pintype "passive"))
      (node (ref "U56") (pin "P22") (pinfunction "IO,_DIFFIO_R27n,_(DQ1R)/(DQ3R)/(DQ1R)_P22") (pintype "bidirectional"))
    )
    (net (code "110") (name "/T_R21") (class "Default")
      (node (ref "P4") (pin "4") (pinfunction "4_4") (pintype "passive"))
      (node (ref "U56") (pin "R21") (pinfunction "IO,_DIFFIO_R29p,_(DQ1R)/(DQ3R)/(DQ1R)_R21") (pintype "bidirectional"))
    )
    (net (code "111") (name "/T_V22") (class "Default")
      (node (ref "P4") (pin "3") (pinfunction "3_3") (pintype "passive"))
      (node (ref "U56") (pin "V22") (pinfunction "IO,_DIFFIO_R34n,_(DQ3R)/(DQ3R)/(DQ1R)_V22") (pintype "bidirectional"))
    )
    (net (code "112") (name "/T_W21") (class "Default")
      (node (ref "P4") (pin "2") (pinfunction "2_2") (pintype "passive"))
      (node (ref "U56") (pin "W21") (pinfunction "IO,_DIFFIO_R37p,_(DQ3R)/(DQ3R)/(DQ1R)_W21") (pintype "bidirectional"))
    )
    (net (code "113") (name "/T_Y22") (class "Default")
      (node (ref "P4") (pin "1") (pinfunction "1_1") (pintype "passive"))
      (node (ref "U56") (pin "Y22") (pinfunction "IO,_DIFFIO_R40n,_(DQ3R)/(DQ3R)/(DQ1R)_Y22") (pintype "bidirectional"))
    )
    (net (code "114") (name "DGND") (class "Default")
      (node (ref "C348") (pin "1") (pinfunction "1_1") (pintype "passive"))
      (node (ref "C349") (pin "1") (pintype "passive"))
      (node (ref "C350") (pin "1") (pintype "passive"))
      (node (ref "C351") (pin "1") (pintype "passive"))
      (node (ref "C352") (pin "1") (pintype "passive"))
      (node (ref "C353") (pin "1") (pintype "passive"))
      (node (ref "C46") (pin "2") (pinfunction "2_2") (pintype "passive"))
      (node (ref "J9") (pin "10") (pinfunction "10_10") (pintype "passive"))
      (node (ref "J9") (pin "2") (pinfunction "2_2") (pintype "passive"))
      (node (ref "R240") (pin "1") (pinfunction "1_1") (pintype "passive"))
      (node (ref "R241") (pin "1") (pinfunction "1_1") (pintype "passive"))
      (node (ref "R242") (pin "2") (pinfunction "2_2") (pintype "passive"))
      (node (ref "U56") (pin "A1") (pinfunction "GND_A1") (pintype "power_in"))
      (node (ref "U56") (pin "A22") (pinfunction "GND_A22") (pintype "power_in"))
      (node (ref "U56") (pin "AA2") (pinfunction "GND_AA2") (pintype "power_in"))
      (node (ref "U56") (pin "AA22") (pinfunction "GND_AA22") (pintype "power_in"))
      (node (ref "U56") (pin "AB1") (pinfunction "GND_AB1") (pintype "power_in"))
      (node (ref "U56") (pin "AB22") (pinfunction "GND_AB22") (pintype "power_in"))
      (node (ref "U56") (pin "C11") (pinfunction "GND_C11") (pintype "power_in"))
      (node (ref "U56") (pin "C12") (pinfunction "GND_C12") (pintype "power_in"))
      (node (ref "U56") (pin "C14") (pinfunction "GND_C14") (pintype "power_in"))
      (node (ref "U56") (pin "C16") (pinfunction "GND_C16") (pintype "power_in"))
      (node (ref "U56") (pin "C5") (pinfunction "GND_C5") (pintype "power_in"))
      (node (ref "U56") (pin "C9") (pinfunction "GND_C9") (pintype "power_in"))
      (node (ref "U56") (pin "D3") (pinfunction "GND_D3") (pintype "power_in"))
      (node (ref "U56") (pin "E10") (pinfunction "GND_E10") (pintype "power_in"))
      (node (ref "U56") (pin "E18") (pinfunction "GNDA2_E18") (pintype "power_in"))
      (node (ref "U56") (pin "E20") (pinfunction "GND_E20") (pintype "power_in"))
      (node (ref "U56") (pin "F12") (pinfunction "GND_F12") (pintype "power_in"))
      (node (ref "U56") (pin "F16") (pinfunction "GND_F16") (pintype "power_in"))
      (node (ref "U56") (pin "F3") (pinfunction "GND_F3") (pintype "power_in"))
      (node (ref "U56") (pin "F5") (pinfunction "GNDA3_F5") (pintype "power_in"))
      (node (ref "U56") (pin "G11") (pinfunction "GND_G11") (pintype "power_in"))
      (node (ref "U56") (pin "G13") (pinfunction "GND_G13") (pintype "power_in"))
      (node (ref "U56") (pin "G15") (pinfunction "GND_G15") (pintype "power_in"))
      (node (ref "U56") (pin "G17") (pinfunction "GND_G17") (pintype "power_in"))
      (node (ref "U56") (pin "G2") (pinfunction "GND_G2") (pintype "power_in"))
      (node (ref "U56") (pin "G20") (pinfunction "GND_G20") (pintype "power_in"))
      (node (ref "U56") (pin "G9") (pinfunction "GND_G9") (pintype "power_in"))
      (node (ref "U56") (pin "H10") (pinfunction "GND_H10") (pintype "power_in"))
      (node (ref "U56") (pin "H12") (pinfunction "GND_H12") (pintype "power_in"))
      (node (ref "U56") (pin "H13") (pinfunction "GND_H13") (pintype "power_in"))
      (node (ref "U56") (pin "H14") (pinfunction "GND_H14") (pintype "power_in"))
      (node (ref "U56") (pin "H16") (pinfunction "GND_H16") (pintype "power_in"))
      (node (ref "U56") (pin "H8") (pinfunction "GND_H8") (pintype "power_in"))
      (node (ref "U56") (pin "J15") (pinfunction "GND_J15") (pintype "power_in"))
      (node (ref "U56") (pin "J9") (pinfunction "GND_J9") (pintype "power_in"))
      (node (ref "U56") (pin "K10") (pinfunction "GND_K10") (pintype "power_in"))
      (node (ref "U56") (pin "K11") (pinfunction "GND_K11") (pintype "power_in"))
      (node (ref "U56") (pin "K12") (pinfunction "GND_K12") (pintype "power_in"))
      (node (ref "U56") (pin "K13") (pinfunction "GND_K13") (pintype "power_in"))
      (node (ref "U56") (pin "K16") (pinfunction "GND_K16") (pintype "power_in"))
      (node (ref "U56") (pin "K3") (pinfunction "GND_K3") (pintype "power_in"))
      (node (ref "U56") (pin "K7") (pinfunction "GND_K7") (pintype "power_in"))
      (node (ref "U56") (pin "L10") (pinfunction "GND_L10") (pintype "power_in"))
      (node (ref "U56") (pin "L11") (pinfunction "GND_L11") (pintype "power_in"))
      (node (ref "U56") (pin "L12") (pinfunction "GND_L12") (pintype "power_in"))
      (node (ref "U56") (pin "L13") (pinfunction "GND_L13") (pintype "power_in"))
      (node (ref "U56") (pin "L15") (pinfunction "GND_L15") (pintype "power_in"))
      (node (ref "U56") (pin "L20") (pinfunction "GND_L20") (pintype "power_in"))
      (node (ref "U56") (pin "L8") (pinfunction "GND_L8") (pintype "power_in"))
      (node (ref "U56") (pin "M10") (pinfunction "GND_M10") (pintype "power_in"))
      (node (ref "U56") (pin "M11") (pinfunction "GND_M11") (pintype "power_in"))
      (node (ref "U56") (pin "M12") (pinfunction "GND_M12") (pintype "power_in"))
      (node (ref "U56") (pin "M13") (pinfunction "GND_M13") (pintype "power_in"))
      (node (ref "U56") (pin "M7") (pinfunction "GND_M7") (pintype "power_in"))
      (node (ref "U56") (pin "N10") (pinfunction "GND_N10") (pintype "power_in"))
      (node (ref "U56") (pin "N11") (pinfunction "GND_N11") (pintype "power_in"))
      (node (ref "U56") (pin "N12") (pinfunction "GND_N12") (pintype "power_in"))
      (node (ref "U56") (pin "N13") (pinfunction "GND_N13") (pintype "power_in"))
      (node (ref "U56") (pin "N15") (pinfunction "GND_N15") (pintype "power_in"))
      (node (ref "U56") (pin "N17") (pinfunction "GND_N17") (pintype "power_in"))
      (node (ref "U56") (pin "N3") (pinfunction "GND_N3") (pintype "power_in"))
      (node (ref "U56") (pin "N8") (pinfunction "GND_N8") (pintype "power_in"))
      (node (ref "U56") (pin "P16") (pinfunction "GND_P16") (pintype "power_in"))
      (node (ref "U56") (pin "P19") (pinfunction "GND_P19") (pintype "power_in"))
      (node (ref "U56") (pin "P6") (pinfunction "GND_P6") (pintype "power_in"))
      (node (ref "U56") (pin "P8") (pinfunction "GND_P8") (pintype "power_in"))
      (node (ref "U56") (pin "R11") (pinfunction "GND_R11") (pintype "power_in"))
      (node (ref "U56") (pin "R13") (pinfunction "GND_R13") (pintype "power_in"))
      (node (ref "U56") (pin "R7") (pinfunction "GND_R7") (pintype "power_in"))
      (node (ref "U56") (pin "R9") (pinfunction "GND_R9") (pintype "power_in"))
      (node (ref "U56") (pin "T10") (pinfunction "GND_T10") (pintype "power_in"))
      (node (ref "U56") (pin "T12") (pinfunction "GND_T12") (pintype "power_in"))
      (node (ref "U56") (pin "T14") (pinfunction "GND_T14") (pintype "power_in"))
      (node (ref "U56") (pin "T8") (pinfunction "GND_T8") (pintype "power_in"))
      (node (ref "U56") (pin "U13") (pinfunction "GND_U13") (pintype "power_in"))
      (node (ref "U56") (pin "U3") (pinfunction "GND_U3") (pintype "power_in"))
      (node (ref "U56") (pin "U5") (pinfunction "GNDA1_U5") (pintype "power_in"))
      (node (ref "U56") (pin "U7") (pinfunction "GND_U7") (pintype "power_in"))
      (node (ref "U56") (pin "V18") (pinfunction "GNDA4_V18") (pintype "power_in"))
      (node (ref "U56") (pin "V20") (pinfunction "GND_V20") (pintype "power_in"))
      (node (ref "U56") (pin "V6") (pinfunction "GND_V6") (pintype "power_in"))
      (node (ref "U56") (pin "W3") (pinfunction "GND_W3") (pintype "power_in"))
      (node (ref "U56") (pin "Y11") (pinfunction "GND_Y11") (pintype "power_in"))
      (node (ref "U56") (pin "Y12") (pinfunction "GND_Y12") (pintype "power_in"))
      (node (ref "U56") (pin "Y16") (pinfunction "GND_Y16") (pintype "power_in"))
      (node (ref "U56") (pin "Y18") (pinfunction "GND_Y18") (pintype "power_in"))
      (node (ref "U56") (pin "Y20") (pinfunction "GND_Y20") (pintype "power_in"))
      (node (ref "U56") (pin "Y5") (pinfunction "GND_Y5") (pintype "power_in"))
      (node (ref "U56") (pin "Y9") (pinfunction "GND_Y9") (pintype "power_in"))
      (node (ref "U59") (pin "2") (pinfunction "GND_2") (pintype "passive"))
      (node (ref "U61") (pin "10") (pinfunction "GND_10") (pintype "passive"))
    )
    (net (code "115") (name "MAIN_+3.3V") (class "Default")
      (node (ref "C348") (pin "2") (pinfunction "2_2") (pintype "passive"))
      (node (ref "C349") (pin "2") (pintype "passive"))
      (node (ref "J9") (pin "6") (pinfunction "6_6") (pintype "passive"))
      (node (ref "R207") (pin "2") (pinfunction "2_2") (pintype "passive"))
      (node (ref "R228") (pin "2") (pinfunction "2_2") (pintype "passive"))
      (node (ref "R229") (pin "2") (pinfunction "2_2") (pintype "passive"))
      (node (ref "R230") (pin "2") (pinfunction "2_2") (pintype "passive"))
      (node (ref "R243") (pin "1") (pinfunction "1_1") (pintype "passive"))
      (node (ref "R244") (pin "1") (pinfunction "1_1") (pintype "passive"))
      (node (ref "R246") (pin "2") (pinfunction "2_2") (pintype "passive"))
      (node (ref "R247") (pin "2") (pinfunction "2_2") (pintype "passive"))
      (node (ref "R64") (pin "2") (pinfunction "2_2") (pintype "passive"))
      (node (ref "R65") (pin "2") (pinfunction "2_2") (pintype "passive"))
      (node (ref "R66") (pin "2") (pinfunction "2_2") (pintype "passive"))
      (node (ref "U56") (pin "A2") (pinfunction "VCCIO8_A2") (pintype "power_in"))
      (node (ref "U56") (pin "A21") (pinfunction "VCCIO7_A21") (pintype "power_in"))
      (node (ref "U56") (pin "AB2") (pinfunction "VCCIO3_AB2") (pintype "power_in"))
      (node (ref "U56") (pin "AB21") (pinfunction "VCCIO4_AB21") (pintype "power_in"))
      (node (ref "U56") (pin "D11") (pinfunction "VCCIO8_D11") (pintype "power_in"))
      (node (ref "U56") (pin "D12") (pinfunction "VCCIO7_D12") (pintype "power_in"))
      (node (ref "U56") (pin "D14") (pinfunction "VCCIO7_D14") (pintype "power_in"))
      (node (ref "U56") (pin "D16") (pinfunction "VCCIO7_D16") (pintype "power_in"))
      (node (ref "U56") (pin "D4") (pinfunction "VCCIO1_D4") (pintype "power_in"))
      (node (ref "U56") (pin "D5") (pinfunction "VCCIO8_D5") (pintype "power_in"))
      (node (ref "U56") (pin "D9") (pinfunction "VCCIO8_D9") (pintype "power_in"))
      (node (ref "U56") (pin "E19") (pinfunction "VCCIO6_E19") (pintype "power_in"))
      (node (ref "U56") (pin "F4") (pinfunction "VCCIO1_F4") (pintype "power_in"))
      (node (ref "U56") (pin "G19") (pinfunction "VCCIO6_G19") (pintype "power_in"))
      (node (ref "U56") (pin "K4") (pinfunction "VCCIO1_K4") (pintype "power_in"))
      (node (ref "U56") (pin "L19") (pinfunction "VCCIO6_L19") (pintype "power_in"))
      (node (ref "U56") (pin "N4") (pinfunction "VCCIO2_N4") (pintype "power_in"))
      (node (ref "U56") (pin "P18") (pinfunction "VCCIO5_P18") (pintype "power_in"))
      (node (ref "U56") (pin "U4") (pinfunction "VCCIO2_U4") (pintype "power_in"))
      (node (ref "U56") (pin "V19") (pinfunction "VCCIO5_V19") (pintype "power_in"))
      (node (ref "U56") (pin "W11") (pinfunction "VCCIO3_W11") (pintype "power_in"))
      (node (ref "U56") (pin "W12") (pinfunction "VCCIO4_W12") (pintype "power_in"))
      (node (ref "U56") (pin "W16") (pinfunction "VCCIO4_W16") (pintype "power_in"))
      (node (ref "U56") (pin "W18") (pinfunction "VCCIO4_W18") (pintype "power_in"))
      (node (ref "U56") (pin "W4") (pinfunction "VCCIO2_W4") (pintype "power_in"))
      (node (ref "U56") (pin "W5") (pinfunction "VCCIO3_W5") (pintype "power_in"))
      (node (ref "U56") (pin "W9") (pinfunction "VCCIO3_W9") (pintype "power_in"))
      (node (ref "U56") (pin "Y19") (pinfunction "VCCIO5_Y19") (pintype "power_in"))
      (node (ref "U59") (pin "4") (pinfunction "VCC_4") (pintype "passive"))
      (node (ref "U61") (pin "1") (pinfunction "VCC_1") (pintype "passive"))
      (node (ref "U61") (pin "2") (pinfunction "VCC_2") (pintype "passive"))
      (node (ref "U61") (pin "9") (pinfunction "VCC_9") (pintype "passive"))
    )
    (net (code "116") (name "Net-(D4-A)") (class "Default")
      (node (ref "D4") (pin "1") (pinfunction "A_1") (pintype "passive"))
      (node (ref "R65") (pin "1") (pinfunction "1_1") (pintype "passive"))
    )
    (net (code "117") (name "Net-(D5-A)") (class "Default")
      (node (ref "D5") (pin "1") (pinfunction "A_1") (pintype "passive"))
      (node (ref "R66") (pin "1") (pinfunction "1_1") (pintype "passive"))
    )
    (net (code "118") (name "Net-(D26-A)") (class "Default")
      (node (ref "D26") (pin "1") (pinfunction "A_1") (pintype "passive"))
      (node (ref "R207") (pin "1") (pinfunction "1_1") (pintype "passive"))
    )
    (net (code "119") (name "Net-(D47-A)") (class "Default")
      (node (ref "D47") (pin "1") (pinfunction "A_1") (pintype "passive"))
      (node (ref "R228") (pin "1") (pinfunction "1_1") (pintype "passive"))
    )
    (net (code "120") (name "Net-(D48-A)") (class "Default")
      (node (ref "D48") (pin "1") (pinfunction "A_1") (pintype "passive"))
      (node (ref "R229") (pin "1") (pinfunction "1_1") (pintype "passive"))
    )
    (net (code "121") (name "Net-(D49-A)") (class "Default")
      (node (ref "D49") (pin "1") (pinfunction "A_1") (pintype "passive"))
      (node (ref "R230") (pin "1") (pinfunction "1_1") (pintype "passive"))
    )
    (net (code "122") (name "Net-(J9-Pad4)") (class "Default")
      (node (ref "J9") (pin "4") (pinfunction "4_4") (pintype "passive"))
      (node (ref "R237") (pin "2") (pinfunction "2_2") (pintype "passive"))
      (node (ref "R238") (pin "2") (pinfunction "2_2") (pintype "passive"))
      (node (ref "R239") (pin "2") (pinfunction "2_2") (pintype "passive"))
    )
    (net (code "123") (name "Net-(T3-TEST)") (class "Default")
      (node (ref "T3") (pin "1") (pinfunction "TEST_1") (pintype "passive"))
      (node (ref "U56") (pin "U1") (pinfunction "IO,_DIFFIO_L27n,_(DQ3L)/(DQ3L)/(DQ1L)_U1") (pintype "bidirectional"))
    )
    (net (code "124") (name "Net-(T4-TEST)") (class "Default")
      (node (ref "T4") (pin "1") (pinfunction "TEST_1") (pintype "passive"))
      (node (ref "U56") (pin "P1") (pinfunction "IO,_DIFFIO_L23n,_(DQ1L)/(DQ3L)/(DQ1L)_P1") (pintype "bidirectional"))
    )
    (net (code "125") (name "Net-(T5-TEST)") (class "Default")
      (node (ref "T5") (pin "1") (pinfunction "TEST_1") (pintype "passive"))
      (node (ref "U56") (pin "V1") (pinfunction "IO,_DIFFIO_L28n,_(DQ3L)/(DQ3L)/(DQ1L)_V1") (pintype "bidirectional"))
    )
    (net (code "126") (name "Net-(T6-TEST)") (class "Default")
      (node (ref "T6") (pin "1") (pinfunction "TEST_1") (pintype "passive"))
      (node (ref "U56") (pin "F1") (pinfunction "IO,_DIFFIO_L9n,_(DQ0L)/(DQ1L)/(DQ1L)_F1") (pintype "bidirectional"))
    )
    (net (code "127") (name "Net-(T7-TEST)") (class "Default")
      (node (ref "T7") (pin "1") (pinfunction "TEST_1") (pintype "passive"))
      (node (ref "U56") (pin "F20") (pinfunction "IO,_DIFFIO_R9n,_(nAVD),_(DQ2R)/(DQ1R)/(DQ1R)_F20") (pintype "bidirectional"))
    )
    (net (code "128") (name "Net-(T8-TEST)") (class "Default")
      (node (ref "T8") (pin "1") (pinfunction "TEST_1") (pintype "passive"))
      (node (ref "U56") (pin "G22") (pinfunction "CLK5,_DIFFCLK_2n_G22") (pintype "input"))
    )
    (net (code "129") (name "Net-(U59-OUT)") (class "Default")
      (node (ref "R235") (pin "1") (pinfunction "1_1") (pintype "passive"))
      (node (ref "U59") (pin "3") (pinfunction "OUT_3") (pintype "passive"))
    )
    (net (code "130") (name "Net-(U61-DATA)") (class "Default")
      (node (ref "C350") (pin "2") (pintype "passive"))
      (node (ref "R248") (pin "2") (pinfunction "2_2") (pintype "passive"))
      (node (ref "U61") (pin "8") (pinfunction "DATA_8") (pintype "passive"))
    )
    (net (code "131") (name "unconnected-(J9-Pad7)") (class "Default")
      (node (ref "J9") (pin "7") (pinfunction "7_7") (pintype "passive+no_connect"))
    )
    (net (code "132") (name "unconnected-(J9-Pad8)") (class "Default")
      (node (ref "J9") (pin "8") (pinfunction "8_8") (pintype "passive+no_connect"))
    )
    (net (code "133") (name "unconnected-(U56A-IO,_DIFFIO_L1n-PadG3)") (class "Default")
      (node (ref "U56") (pin "G3") (pinfunction "IO,_DIFFIO_L1n_G3") (pintype "bidirectional"))
    )
    (net (code "134") (name "unconnected-(U56A-IO,_DIFFIO_L1p-PadG4)") (class "Default")
      (node (ref "U56") (pin "G4") (pinfunction "IO,_DIFFIO_L1p_G4") (pintype "bidirectional"))
    )
    (net (code "135") (name "unconnected-(U56A-IO,_DIFFIO_L3n,_(DQ2L){slash}(DQ1L){slash}(DQ1L)-PadE3)") (class "Default")
      (node (ref "U56") (pin "E3") (pinfunction "IO,_DIFFIO_L3n,_(DQ2L)/(DQ1L)/(DQ1L)_E3") (pintype "bidirectional"))
    )
    (net (code "136") (name "unconnected-(U56A-IO,_DIFFIO_L3p,_(nRESET),_(DQ2L){slash}(DQ1L){slash}(DQ1L)-PadE4)") (class "Default")
      (node (ref "U56") (pin "E4") (pinfunction "IO,_DIFFIO_L3p,_(nRESET),_(DQ2L)/(DQ1L)/(DQ1L)_E4") (pintype "bidirectional"))
    )
    (net (code "137") (name "unconnected-(U56A-IO,_DIFFIO_L5p,_(DQ2L){slash}(DQ1L){slash}(DQ1L)-PadD2)") (class "Default")
      (node (ref "U56") (pin "D2") (pinfunction "IO,_DIFFIO_L5p,_(DQ2L)/(DQ1L)/(DQ1L)_D2") (pintype "bidirectional"))
    )
    (net (code "138") (name "unconnected-(U56A-IO,_DIFFIO_L6n,_(DQ2L){slash}(DQ1L){slash}(DQ1L)-PadJ6)") (class "Default")
      (node (ref "U56") (pin "J6") (pinfunction "IO,_DIFFIO_L6n,_(DQ2L)/(DQ1L)/(DQ1L)_J6") (pintype "bidirectional"))
    )
    (net (code "139") (name "unconnected-(U56A-IO,_DIFFIO_L6p,_(DQ2L){slash}(DQ1L){slash}(DQ1L)-PadH6)") (class "Default")
      (node (ref "U56") (pin "H6") (pinfunction "IO,_DIFFIO_L6p,_(DQ2L)/(DQ1L)/(DQ1L)_H6") (pintype "bidirectional"))
    )
    (net (code "140") (name "unconnected-(U56A-IO,_DIFFIO_L7n-PadH3)") (class "Default")
      (node (ref "U56") (pin "H3") (pinfunction "IO,_DIFFIO_L7n_H3") (pintype "bidirectional"))
    )
    (net (code "141") (name "unconnected-(U56A-IO,_DIFFIO_L7p-PadH4)") (class "Default")
      (node (ref "U56") (pin "H4") (pinfunction "IO,_DIFFIO_L7p_H4") (pintype "bidirectional"))
    )
    (net (code "142") (name "unconnected-(U56A-IO,_DIFFIO_L8n,_(_){slash}(DQ1L){slash}(DQ1L)-PadE1)") (class "Default")
      (node (ref "U56") (pin "E1") (pinfunction "IO,_DIFFIO_L8n,_(_)/(DQ1L)/(DQ1L)_E1") (pintype "bidirectional"))
    )
    (net (code "143") (name "unconnected-(U56A-IO,_DIFFIO_L9p,_(DM2L){slash}(DM1L{slash}BWS#1L){slash}(DM1L{slash}BWS#1L)-PadF2)") (class "Default")
      (node (ref "U56") (pin "F2") (pinfunction "IO,_DIFFIO_L9p,_(DM2L)/(DM1L/BWS#1L)/(DM1L/BWS#1L)_F2") (pintype "bidirectional"))
    )
    (net (code "144") (name "unconnected-(U56A-IO,_DIFFIO_L12p,_(DQS0L{slash}CQ1L,DPCLK0){slash}(DQS0L{slash}CQ1L,DPCLK0){slash}(DQS0L{slash}CQ1L,DPCLK0)-PadJ4)") (class "Default")
      (node (ref "U56") (pin "J4") (pinfunction "IO,_DIFFIO_L12p,_(DQS0L/CQ1L,DPCLK0)/(DQS0L/CQ1L,DPCLK0)/(DQS0L/CQ1L,DPCLK0)_J4") (pintype "bidirectional"))
    )
    (net (code "145") (name "unconnected-(U56A-IO,_DIFFIO_L13n,_(DQ0L){slash}(DQ1L){slash}(DQ1L)-PadH1)") (class "Default")
      (node (ref "U56") (pin "H1") (pinfunction "IO,_DIFFIO_L13n,_(DQ0L)/(DQ1L)/(DQ1L)_H1") (pintype "bidirectional"))
    )
    (net (code "146") (name "unconnected-(U56A-IO,_DIFFIO_L13p,_(DQ0L){slash}(DQ1L){slash}(DQ1L)-PadH2)") (class "Default")
      (node (ref "U56") (pin "H2") (pinfunction "IO,_DIFFIO_L13p,_(DQ0L)/(DQ1L)/(DQ1L)_H2") (pintype "bidirectional"))
    )
    (net (code "147") (name "unconnected-(U56A-IO,_DIFFIO_L17n,_(DQ0L){slash}(DQ1L){slash}(DQ1L)-PadJ1)") (class "Default")
      (node (ref "U56") (pin "J1") (pinfunction "IO,_DIFFIO_L17n,_(DQ0L)/(DQ1L)/(DQ1L)_J1") (pintype "bidirectional"))
    )
    (net (code "148") (name "unconnected-(U56A-IO,_VREFB1N0-PadG5)") (class "Default")
      (node (ref "U56") (pin "G5") (pinfunction "IO,_VREFB1N0_G5") (pintype "bidirectional"))
    )
    (net (code "149") (name "unconnected-(U56A-IO,_VREFB1N1-PadH5)") (class "Default")
      (node (ref "U56") (pin "H5") (pinfunction "IO,_VREFB1N1_H5") (pintype "bidirectional"))
    )
    (net (code "150") (name "unconnected-(U56A-IO,_VREFB1N2-PadJ3)") (class "Default")
      (node (ref "U56") (pin "J3") (pinfunction "IO,_VREFB1N2_J3") (pintype "bidirectional"))
    )
    (net (code "151") (name "unconnected-(U56A-IO-PadH7)") (class "Default")
      (node (ref "U56") (pin "H7") (pinfunction "IO_H7") (pintype "bidirectional"))
    )
    (net (code "152") (name "unconnected-(U56A-IO-PadJ5)") (class "Default")
      (node (ref "U56") (pin "J5") (pinfunction "IO_J5") (pintype "bidirectional"))
    )
    (net (code "153") (name "unconnected-(U56B-IO,_DIFFIO_L19n,_(DQ0L){slash}(DQ1L){slash}(DQ1L)-PadM6)") (class "Default")
      (node (ref "U56") (pin "M6") (pinfunction "IO,_DIFFIO_L19n,_(DQ0L)/(DQ1L)/(DQ1L)_M6") (pintype "bidirectional"))
    )
    (net (code "154") (name "unconnected-(U56B-IO,_DIFFIO_L19p,_(DQ0L){slash}(DQ1L){slash}(DQ1L)-PadL6)") (class "Default")
      (node (ref "U56") (pin "L6") (pinfunction "IO,_DIFFIO_L19p,_(DQ0L)/(DQ1L)/(DQ1L)_L6") (pintype "bidirectional"))
    )
    (net (code "155") (name "unconnected-(U56B-IO,_DIFFIO_L20p,_(DQ0L){slash}(DQ1L){slash}(DQ1L)-PadM2)") (class "Default")
      (node (ref "U56") (pin "M2") (pinfunction "IO,_DIFFIO_L20p,_(DQ0L)/(DQ1L)/(DQ1L)_M2") (pintype "bidirectional"))
    )
    (net (code "156") (name "unconnected-(U56B-IO,_DIFFIO_L21n,_(DQ1L){slash}(DQ3L){slash}(DQ1L)-PadM3)") (class "Default")
      (node (ref "U56") (pin "M3") (pinfunction "IO,_DIFFIO_L21n,_(DQ1L)/(DQ3L)/(DQ1L)_M3") (pintype "bidirectional"))
    )
    (net (code "157") (name "unconnected-(U56B-IO,_DIFFIO_L21p,_(DM0L){slash}(DM1L{slash}BWS#1L){slash}(DM1L{slash}BWS#1L)-PadM4)") (class "Default")
      (node (ref "U56") (pin "M4") (pinfunction "IO,_DIFFIO_L21p,_(DM0L)/(DM1L/BWS#1L)/(DM1L/BWS#1L)_M4") (pintype "bidirectional"))
    )
    (net (code "158") (name "unconnected-(U56B-IO,_DIFFIO_L22n,_(DQ1L){slash}(DQ3L){slash}(DQ1L)-PadN1)") (class "Default")
      (node (ref "U56") (pin "N1") (pinfunction "IO,_DIFFIO_L22n,_(DQ1L)/(DQ3L)/(DQ1L)_N1") (pintype "bidirectional"))
    )
    (net (code "159") (name "unconnected-(U56B-IO,_DIFFIO_L22p,_(DQ1L){slash}(DQ3L){slash}(DQ1L)-PadN2)") (class "Default")
      (node (ref "U56") (pin "N2") (pinfunction "IO,_DIFFIO_L22p,_(DQ1L)/(DQ3L)/(DQ1L)_N2") (pintype "bidirectional"))
    )
    (net (code "160") (name "unconnected-(U56B-IO,_DIFFIO_L23p,_(DQ1L){slash}(DQ3L){slash}(DQ1L)-PadP2)") (class "Default")
      (node (ref "U56") (pin "P2") (pinfunction "IO,_DIFFIO_L23p,_(DQ1L)/(DQ3L)/(DQ1L)_P2") (pintype "bidirectional"))
    )
    (net (code "161") (name "unconnected-(U56B-IO,_DIFFIO_L24n,_(DQ1L){slash}(DQ3L){slash}(DQ1L)-PadR1)") (class "Default")
      (node (ref "U56") (pin "R1") (pinfunction "IO,_DIFFIO_L24n,_(DQ1L)/(DQ3L)/(DQ1L)_R1") (pintype "bidirectional"))
    )
    (net (code "162") (name "unconnected-(U56B-IO,_DIFFIO_L24p,_(DQ1L){slash}(DQ3L){slash}(DQ1L)-PadR2)") (class "Default")
      (node (ref "U56") (pin "R2") (pinfunction "IO,_DIFFIO_L24p,_(DQ1L)/(DQ3L)/(DQ1L)_R2") (pintype "bidirectional"))
    )
    (net (code "163") (name "unconnected-(U56B-IO,_DIFFIO_L25n,_(DQ1L){slash}(DQ3L){slash}(DQ1L)-PadN5)") (class "Default")
      (node (ref "U56") (pin "N5") (pinfunction "IO,_DIFFIO_L25n,_(DQ1L)/(DQ3L)/(DQ1L)_N5") (pintype "bidirectional"))
    )
    (net (code "164") (name "unconnected-(U56B-IO,_DIFFIO_L26n,_(DQ1L){slash}(DQ3L){slash}(DQ1L)-PadP3)") (class "Default")
      (node (ref "U56") (pin "P3") (pinfunction "IO,_DIFFIO_L26n,_(DQ1L)/(DQ3L)/(DQ1L)_P3") (pintype "bidirectional"))
    )
    (net (code "165") (name "unconnected-(U56B-IO,_DIFFIO_L26p,_(DQS1L{slash}CQ1L#,DPCLK1){slash}(DQS1L{slash}CQ1L#,DPCLK1){slash}(DQS1L{slash}CQ1L#,DPCLK1)-PadP4)") (class "Default")
      (node (ref "U56") (pin "P4") (pinfunction "IO,_DIFFIO_L26p,_(DQS1L/CQ1L#,DPCLK1)/(DQS1L/CQ1L#,DPCLK1)/(DQS1L/CQ1L#,DPCLK1)_P4") (pintype "bidirectional"))
    )
    (net (code "166") (name "unconnected-(U56B-IO,_DIFFIO_L27p,_(DM1L{slash}BWS#1L){slash}(DM3L{slash}BWS#3L){slash}(DM1L{slash}BWS#1L)-PadU2)") (class "Default")
      (node (ref "U56") (pin "U2") (pinfunction "IO,_DIFFIO_L27p,_(DM1L/BWS#1L)/(DM3L/BWS#3L)/(DM1L/BWS#1L)_U2") (pintype "bidirectional"))
    )
    (net (code "167") (name "unconnected-(U56B-IO,_DIFFIO_L28p,_(DQ3L){slash}(DQ3L){slash}(DQ1L)-PadV2)") (class "Default")
      (node (ref "U56") (pin "V2") (pinfunction "IO,_DIFFIO_L28p,_(DQ3L)/(DQ3L)/(DQ1L)_V2") (pintype "bidirectional"))
    )
    (net (code "168") (name "unconnected-(U56B-IO,_DIFFIO_L29n,_(DQ3L){slash}(DQ3L){slash}(DQ1L)-PadN6)") (class "Default")
      (node (ref "U56") (pin "N6") (pinfunction "IO,_DIFFIO_L29n,_(DQ3L)/(DQ3L)/(DQ1L)_N6") (pintype "bidirectional"))
    )
    (net (code "169") (name "unconnected-(U56B-IO,_DIFFIO_L29p-PadP5)") (class "Default")
      (node (ref "U56") (pin "P5") (pinfunction "IO,_DIFFIO_L29p_P5") (pintype "bidirectional"))
    )
    (net (code "170") (name "unconnected-(U56B-IO,_DIFFIO_L30n-PadR3)") (class "Default")
      (node (ref "U56") (pin "R3") (pinfunction "IO,_DIFFIO_L30n_R3") (pintype "bidirectional"))
    )
    (net (code "171") (name "unconnected-(U56B-IO,_DIFFIO_L30p-PadR4)") (class "Default")
      (node (ref "U56") (pin "R4") (pinfunction "IO,_DIFFIO_L30p_R4") (pintype "bidirectional"))
    )
    (net (code "172") (name "unconnected-(U56B-IO,_DIFFIO_L31p,_(DQ3L){slash}(DQ3L){slash}(DQ1L)-PadW2)") (class "Default")
      (node (ref "U56") (pin "W2") (pinfunction "IO,_DIFFIO_L31p,_(DQ3L)/(DQ3L)/(DQ1L)_W2") (pintype "bidirectional"))
    )
    (net (code "173") (name "unconnected-(U56B-IO,_DIFFIO_L32p,_(DQ3L){slash}(DQ3L){slash}(DQ1L)-PadY2)") (class "Default")
      (node (ref "U56") (pin "Y2") (pinfunction "IO,_DIFFIO_L32p,_(DQ3L)/(DQ3L)/(DQ1L)_Y2") (pintype "bidirectional"))
    )
    (net (code "174") (name "unconnected-(U56B-IO,_DIFFIO_L35n,_(DM3L{slash}BWS#3L){slash}(DM3L{slash}BWS#3L){slash}(DM1L{slash}BWS#1L)-PadT5)") (class "Default")
      (node (ref "U56") (pin "T5") (pinfunction "IO,_DIFFIO_L35n,_(DM3L/BWS#3L)/(DM3L/BWS#3L)/(DM1L/BWS#1L)_T5") (pintype "bidirectional"))
    )
    (net (code "175") (name "unconnected-(U56B-IO,_DIFFIO_L35p,_(DQS3L{slash}CQ3L#,CDPCLK1){slash}(DQS3L{slash}CQ3L#,CDPCLK1){slash}(DQS3L{slash}CQ3L#,CDPCLK1)-PadT4)") (class "Default")
      (node (ref "U56") (pin "T4") (pinfunction "IO,_DIFFIO_L35p,_(DQS3L/CQ3L#,CDPCLK1)/(DQS3L/CQ3L#,CDPCLK1)/(DQS3L/CQ3L#,CDPCLK1)_T4") (pintype "bidirectional"))
    )
    (net (code "176") (name "unconnected-(U56B-IO,_RDN1-PadV3)") (class "Default")
      (node (ref "U56") (pin "V3") (pinfunction "IO,_RDN1_V3") (pintype "bidirectional"))
    )
    (net (code "177") (name "unconnected-(U56B-IO,_RUP1-PadV4)") (class "Default")
      (node (ref "U56") (pin "V4") (pinfunction "IO,_RUP1_V4") (pintype "bidirectional"))
    )
    (net (code "178") (name "unconnected-(U56B-IO,_VREFB2N0-PadM5)") (class "Default")
      (node (ref "U56") (pin "M5") (pinfunction "IO,_VREFB2N0_M5") (pintype "bidirectional"))
    )
    (net (code "179") (name "unconnected-(U56B-IO,_VREFB2N1-PadT3)") (class "Default")
      (node (ref "U56") (pin "T3") (pinfunction "IO,_VREFB2N1_T3") (pintype "bidirectional"))
    )
    (net (code "180") (name "unconnected-(U56B-IO,_VREFB2N2-PadR5)") (class "Default")
      (node (ref "U56") (pin "R5") (pinfunction "IO,_VREFB2N2_R5") (pintype "bidirectional"))
    )
    (net (code "181") (name "unconnected-(U56C-IO,_(DQ3B){slash}(DQ3B){slash}(DQ5B)-PadAA4)") (class "Default")
      (node (ref "U56") (pin "AA4") (pinfunction "IO,_(DQ3B)/(DQ3B)/(DQ5B)_AA4") (pintype "bidirectional"))
    )
    (net (code "182") (name "unconnected-(U56C-IO,_(DQ3B){slash}(DQ3B){slash}(DQ5B)-PadW8)") (class "Default")
      (node (ref "U56") (pin "W8") (pinfunction "IO,_(DQ3B)/(DQ3B)/(DQ5B)_W8") (pintype "bidirectional"))
    )
    (net (code "183") (name "unconnected-(U56C-IO,_(DQ5B){slash}(DQ3B){slash}(DQ5B)-PadV11)") (class "Default")
      (node (ref "U56") (pin "V11") (pinfunction "IO,_(DQ5B)/(DQ3B)/(DQ5B)_V11") (pintype "bidirectional"))
    )
    (net (code "184") (name "unconnected-(U56C-IO,_(DQS1B{slash}CQ1B#,CDPCLK2){slash}(DQS1B{slash}CQ1B#,CDPCLK2){slash}(DQS1B{slash}CQ1B#,CDPCLK2)-PadY6)") (class "Default")
      (node (ref "U56") (pin "Y6") (pinfunction "IO,_(DQS1B/CQ1B#,CDPCLK2)/(DQS1B/CQ1B#,CDPCLK2)/(DQS1B/CQ1B#,CDPCLK2)_Y6") (pintype "bidirectional"))
    )
    (net (code "185") (name "unconnected-(U56C-IO,_DIFFIO_B1n,_(DM3B{slash}BWS#3B){slash}(DM3B{slash}BWS#3B){slash}(DM5B{slash}BWS#5B)-PadV5)") (class "Default")
      (node (ref "U56") (pin "V5") (pinfunction "IO,_DIFFIO_B1n,_(DM3B/BWS#3B)/(DM3B/BWS#3B)/(DM5B/BWS#5B)_V5") (pintype "bidirectional"))
    )
    (net (code "186") (name "unconnected-(U56C-IO,_DIFFIO_B3n,_(DQ3B){slash}(DQ3B){slash}(DQ5B)-PadY3)") (class "Default")
      (node (ref "U56") (pin "Y3") (pinfunction "IO,_DIFFIO_B3n,_(DQ3B)/(DQ3B)/(DQ5B)_Y3") (pintype "bidirectional"))
    )
    (net (code "187") (name "unconnected-(U56C-IO,_DIFFIO_B3p-PadY4)") (class "Default")
      (node (ref "U56") (pin "Y4") (pinfunction "IO,_DIFFIO_B3p_Y4") (pintype "bidirectional"))
    )
    (net (code "188") (name "unconnected-(U56C-IO,_DIFFIO_B4p,_(DQ3B){slash}(DQ3B){slash}(DQ5B)-PadW6)") (class "Default")
      (node (ref "U56") (pin "W6") (pinfunction "IO,_DIFFIO_B4p,_(DQ3B)/(DQ3B)/(DQ5B)_W6") (pintype "bidirectional"))
    )
    (net (code "189") (name "unconnected-(U56C-IO,_DIFFIO_B5n-PadAA6)") (class "Default")
      (node (ref "U56") (pin "AA6") (pinfunction "IO,_DIFFIO_B5n_AA6") (pintype "bidirectional"))
    )
    (net (code "190") (name "unconnected-(U56C-IO,_DIFFIO_B5p,_(DQ3B){slash}(DQ3B){slash}(DQ5B)-PadAA5)") (class "Default")
      (node (ref "U56") (pin "AA5") (pinfunction "IO,_DIFFIO_B5p,_(DQ3B)/(DQ3B)/(DQ5B)_AA5") (pintype "bidirectional"))
    )
    (net (code "191") (name "unconnected-(U56C-IO,_DIFFIO_B7n,_(DQ3B){slash}(DQ3B){slash}(DQ5B)-PadY7)") (class "Default")
      (node (ref "U56") (pin "Y7") (pinfunction "IO,_DIFFIO_B7n,_(DQ3B)/(DQ3B)/(DQ5B)_Y7") (pintype "bidirectional"))
    )
    (net (code "192") (name "unconnected-(U56C-IO,_DIFFIO_B7p,_(DQ3B){slash}(DQ3B){slash}(DQ5B)-PadW7)") (class "Default")
      (node (ref "U56") (pin "W7") (pinfunction "IO,_DIFFIO_B7p,_(DQ3B)/(DQ3B)/(DQ5B)_W7") (pintype "bidirectional"))
    )
    (net (code "193") (name "unconnected-(U56C-IO,_DIFFIO_B8n,_(DQ3B){slash}(DQ3B){slash}(DQ5B)-PadV8)") (class "Default")
      (node (ref "U56") (pin "V8") (pinfunction "IO,_DIFFIO_B8n,_(DQ3B)/(DQ3B)/(DQ5B)_V8") (pintype "bidirectional"))
    )
    (net (code "194") (name "unconnected-(U56C-IO,_DIFFIO_B8p,_(DQ3B){slash}(DQ3B){slash}(DQ5B)-PadU9)") (class "Default")
      (node (ref "U56") (pin "U9") (pinfunction "IO,_DIFFIO_B8p,_(DQ3B)/(DQ3B)/(DQ5B)_U9") (pintype "bidirectional"))
    )
    (net (code "195") (name "unconnected-(U56C-IO,_DIFFIO_B10p,_(DM5B{slash}BWS#5B){slash}(DM3B{slash}BWS#3B){slash}(DM5B{slash}BWS#5B)-PadAA7)") (class "Default")
      (node (ref "U56") (pin "AA7") (pinfunction "IO,_DIFFIO_B10p,_(DM5B/BWS#5B)/(DM3B/BWS#3B)/(DM5B/BWS#5B)_AA7") (pintype "bidirectional"))
    )
    (net (code "196") (name "unconnected-(U56C-IO,_DIFFIO_B11p,_(DQ5B){slash}(DQ3B){slash}(DQ5B)-PadY8)") (class "Default")
      (node (ref "U56") (pin "Y8") (pinfunction "IO,_DIFFIO_B11p,_(DQ5B)/(DQ3B)/(DQ5B)_Y8") (pintype "bidirectional"))
    )
    (net (code "197") (name "unconnected-(U56C-IO,_DIFFIO_B15p,_(DQS3B{slash}CQ3B#,DPCLK2){slash}(DQS3B{slash}CQ3B#,DPCLK2){slash}(DQS3B{slash}CQ3B#,DPCLK2)-PadV10)") (class "Default")
      (node (ref "U56") (pin "V10") (pinfunction "IO,_DIFFIO_B15p,_(DQS3B/CQ3B#,DPCLK2)/(DQS3B/CQ3B#,DPCLK2)/(DQS3B/CQ3B#,DPCLK2)_V10") (pintype "bidirectional"))
    )
    (net (code "198") (name "unconnected-(U56C-IO,_DIFFIO_B16n,_(DQ5B){slash}(DQ3B){slash}(DQ5B)-PadU10)") (class "Default")
      (node (ref "U56") (pin "U10") (pinfunction "IO,_DIFFIO_B16n,_(DQ5B)/(DQ3B)/(DQ5B)_U10") (pintype "bidirectional"))
    )
    (net (code "199") (name "unconnected-(U56C-IO,_DIFFIO_B22n,_(DQ5B){slash}(DQ3B){slash}(DQ5B)-PadY10)") (class "Default")
      (node (ref "U56") (pin "Y10") (pinfunction "IO,_DIFFIO_B22n,_(DQ5B)/(DQ3B)/(DQ5B)_Y10") (pintype "bidirectional"))
    )
    (net (code "200") (name "unconnected-(U56C-IO,_DIFFIO_B22p,_(DQ5B){slash}(DQ3B){slash}(DQ5B)-PadW10)") (class "Default")
      (node (ref "U56") (pin "W10") (pinfunction "IO,_DIFFIO_B22p,_(DQ5B)/(DQ3B)/(DQ5B)_W10") (pintype "bidirectional"))
    )
    (net (code "201") (name "unconnected-(U56C-IO,_PLL1_CLKOUTn-PadAB3)") (class "Default")
      (node (ref "U56") (pin "AB3") (pinfunction "IO,_PLL1_CLKOUTn_AB3") (pintype "bidirectional"))
    )
    (net (code "202") (name "unconnected-(U56C-IO,_PLL1_CLKOUTp-PadAA3)") (class "Default")
      (node (ref "U56") (pin "AA3") (pinfunction "IO,_PLL1_CLKOUTp_AA3") (pintype "bidirectional"))
    )
    (net (code "203") (name "unconnected-(U56C-IO,_VREFB3N0-PadU11)") (class "Default")
      (node (ref "U56") (pin "U11") (pinfunction "IO,_VREFB3N0_U11") (pintype "bidirectional"))
    )
    (net (code "204") (name "unconnected-(U56C-IO,_VREFB3N1-PadV9)") (class "Default")
      (node (ref "U56") (pin "V9") (pinfunction "IO,_VREFB3N1_V9") (pintype "bidirectional"))
    )
    (net (code "205") (name "unconnected-(U56C-IO,_VREFB3N2-PadAB4)") (class "Default")
      (node (ref "U56") (pin "AB4") (pinfunction "IO,_VREFB3N2_AB4") (pintype "bidirectional"))
    )
    (net (code "206") (name "unconnected-(U56D-IO,_DIFFIO_B28n,_(DQS4B{slash}CQ5B,DPCLK4){slash}(DQS4B{slash}CQ5B,DPCLK4){slash}(DQS4B{slash}CQ5B,DPCLK4)-PadY13)") (class "Default")
      (node (ref "U56") (pin "Y13") (pinfunction "IO,_DIFFIO_B28n,_(DQS4B/CQ5B,DPCLK4)/(DQS4B/CQ5B,DPCLK4)/(DQS4B/CQ5B,DPCLK4)_Y13") (pintype "bidirectional"))
    )
    (net (code "207") (name "unconnected-(U56D-IO,_DIFFIO_B28p,_(DQ4B){slash}(DQ5B){slash}(DQ5B)-PadW13)") (class "Default")
      (node (ref "U56") (pin "W13") (pinfunction "IO,_DIFFIO_B28p,_(DQ4B)/(DQ5B)/(DQ5B)_W13") (pintype "bidirectional"))
    )
    (net (code "208") (name "unconnected-(U56D-IO,_DIFFIO_B30p,_(DQ4B){slash}(DQ5B){slash}(DQ5B)-PadU12)") (class "Default")
      (node (ref "U56") (pin "U12") (pinfunction "IO,_DIFFIO_B30p,_(DQ4B)/(DQ5B)/(DQ5B)_U12") (pintype "bidirectional"))
    )
    (net (code "209") (name "unconnected-(U56D-IO,_DIFFIO_B31n-PadY15)") (class "Default")
      (node (ref "U56") (pin "Y15") (pinfunction "IO,_DIFFIO_B31n_Y15") (pintype "bidirectional"))
    )
    (net (code "210") (name "unconnected-(U56D-IO,_DIFFIO_B31p-PadY14)") (class "Default")
      (node (ref "U56") (pin "Y14") (pinfunction "IO,_DIFFIO_B31p_Y14") (pintype "bidirectional"))
    )
    (net (code "211") (name "unconnected-(U56D-IO,_DIFFIO_B33n-PadW14)") (class "Default")
      (node (ref "U56") (pin "W14") (pinfunction "IO,_DIFFIO_B33n_W14") (pintype "bidirectional"))
    )
    (net (code "212") (name "unconnected-(U56D-IO,_DIFFIO_B33p,_(DQS2B{slash}CQ3B,DPCLK5){slash}(DQS2B{slash}CQ3B,DPCLK5){slash}(DQS2B{slash}CQ3B,DPCLK5)-PadV13)") (class "Default")
      (node (ref "U56") (pin "V13") (pinfunction "IO,_DIFFIO_B33p,_(DQS2B/CQ3B,DPCLK5)/(DQS2B/CQ3B,DPCLK5)/(DQS2B/CQ3B,DPCLK5)_V13") (pintype "bidirectional"))
    )
    (net (code "213") (name "unconnected-(U56D-IO,_DIFFIO_B35n-PadU14)") (class "Default")
      (node (ref "U56") (pin "U14") (pinfunction "IO,_DIFFIO_B35n_U14") (pintype "bidirectional"))
    )
    (net (code "214") (name "unconnected-(U56D-IO,_DIFFIO_B35p,_(DQ2B){slash}(DQ5B){slash}(DQ5B)-PadV14)") (class "Default")
      (node (ref "U56") (pin "V14") (pinfunction "IO,_DIFFIO_B35p,_(DQ2B)/(DQ5B)/(DQ5B)_V14") (pintype "bidirectional"))
    )
    (net (code "215") (name "unconnected-(U56D-IO,_DIFFIO_B36n,_(DQ2B){slash}(DQ5B){slash}(DQ5B)-PadV15)") (class "Default")
      (node (ref "U56") (pin "V15") (pinfunction "IO,_DIFFIO_B36n,_(DQ2B)/(DQ5B)/(DQ5B)_V15") (pintype "bidirectional"))
    )
    (net (code "216") (name "unconnected-(U56D-IO,_DIFFIO_B36p-PadU15)") (class "Default")
      (node (ref "U56") (pin "U15") (pinfunction "IO,_DIFFIO_B36p_U15") (pintype "bidirectional"))
    )
    (net (code "217") (name "unconnected-(U56D-IO,_DIFFIO_B37p,_(DQ2B){slash}(DQ5B){slash}(DQ5B)-PadW15)") (class "Default")
      (node (ref "U56") (pin "W15") (pinfunction "IO,_DIFFIO_B37p,_(DQ2B)/(DQ5B)/(DQ5B)_W15") (pintype "bidirectional"))
    )
    (net (code "218") (name "unconnected-(U56D-IO,_DIFFIO_B38n,_(DQ2B){slash}(DQ5B){slash}(DQ5B)-PadT15)") (class "Default")
      (node (ref "U56") (pin "T15") (pinfunction "IO,_DIFFIO_B38n,_(DQ2B)/(DQ5B)/(DQ5B)_T15") (pintype "bidirectional"))
    )
    (net (code "219") (name "unconnected-(U56D-IO,_DIFFIO_B40n,_(DQS0B{slash}CQ1B,CDPCLK3){slash}(DQS0B{slash}CQ1B,CDPCLK3){slash}(DQS0B{slash}CQ1B,CDPCLK3)-PadY17)") (class "Default")
      (node (ref "U56") (pin "Y17") (pinfunction "IO,_DIFFIO_B40n,_(DQS0B/CQ1B,CDPCLK3)/(DQS0B/CQ1B,CDPCLK3)/(DQS0B/CQ1B,CDPCLK3)_Y17") (pintype "bidirectional"))
    )
    (net (code "220") (name "unconnected-(U56D-IO,_DIFFIO_B40p,_(DQ2B){slash}(DQ5B){slash}(DQ5B)-PadW17)") (class "Default")
      (node (ref "U56") (pin "W17") (pinfunction "IO,_DIFFIO_B40p,_(DQ2B)/(DQ5B)/(DQ5B)_W17") (pintype "bidirectional"))
    )
    (net (code "221") (name "unconnected-(U56D-IO,_DIFFIO_B41p,_(_){slash}(DQ5B){slash}(DQ5B)-PadAA20)") (class "Default")
      (node (ref "U56") (pin "AA20") (pinfunction "IO,_DIFFIO_B41p,_(_)/(DQ5B)/(DQ5B)_AA20") (pintype "bidirectional"))
    )
    (net (code "222") (name "unconnected-(U56D-IO,_DIFFIO_B44n-PadU17)") (class "Default")
      (node (ref "U56") (pin "U17") (pinfunction "IO,_DIFFIO_B44n_U17") (pintype "bidirectional"))
    )
    (net (code "223") (name "unconnected-(U56D-IO,_DIFFIO_B44p-PadU16)") (class "Default")
      (node (ref "U56") (pin "U16") (pinfunction "IO,_DIFFIO_B44p_U16") (pintype "bidirectional"))
    )
    (net (code "224") (name "unconnected-(U56D-IO,_DIFFIO_B45p-PadR14)") (class "Default")
      (node (ref "U56") (pin "R14") (pinfunction "IO,_DIFFIO_B45p_R14") (pintype "bidirectional"))
    )
    (net (code "225") (name "unconnected-(U56D-IO,_PLL4_CLKOUTn-PadR16)") (class "Default")
      (node (ref "U56") (pin "R16") (pinfunction "IO,_PLL4_CLKOUTn_R16") (pintype "bidirectional"))
    )
    (net (code "226") (name "unconnected-(U56D-IO,_PLL4_CLKOUTp-PadT16)") (class "Default")
      (node (ref "U56") (pin "T16") (pinfunction "IO,_PLL4_CLKOUTp_T16") (pintype "bidirectional"))
    )
    (net (code "227") (name "unconnected-(U56D-IO,_RUP2-PadAA19)") (class "Default")
      (node (ref "U56") (pin "AA19") (pinfunction "IO,_RUP2_AA19") (pintype "bidirectional"))
    )
    (net (code "228") (name "unconnected-(U56D-IO,_VREFB4N0-PadV16)") (class "Default")
      (node (ref "U56") (pin "V16") (pinfunction "IO,_VREFB4N0_V16") (pintype "bidirectional"))
    )
    (net (code "229") (name "unconnected-(U56D-IO,_VREFB4N1-PadAA18)") (class "Default")
      (node (ref "U56") (pin "AA18") (pinfunction "IO,_VREFB4N1_AA18") (pintype "bidirectional"))
    )
    (net (code "230") (name "unconnected-(U56D-IO,_VREFB4N2-PadV12)") (class "Default")
      (node (ref "U56") (pin "V12") (pinfunction "IO,_VREFB4N2_V12") (pintype "bidirectional"))
    )
    (net (code "231") (name "unconnected-(U56E-IO,_(DQS3R{slash}CQ3R#,CDPCLK4){slash}(DQS3R{slash}CQ3R#,CDPCLK4){slash}(DQS3R{slash}CQ3R#,CDPCLK4)-PadW20)") (class "Default")
      (node (ref "U56") (pin "W20") (pinfunction "IO,_(DQS3R/CQ3R#,CDPCLK4)/(DQS3R/CQ3R#,CDPCLK4)/(DQS3R/CQ3R#,CDPCLK4)_W20") (pintype "bidirectional"))
    )
    (net (code "232") (name "unconnected-(U56E-IO,_DIFFIO_R21n,_(DQ1R){slash}(DQ3R){slash}(DQ1R)-PadM20)") (class "Default")
      (node (ref "U56") (pin "M20") (pinfunction "IO,_DIFFIO_R21n,_(DQ1R)/(DQ3R)/(DQ1R)_M20") (pintype "bidirectional"))
    )
    (net (code "233") (name "unconnected-(U56E-IO,_DIFFIO_R21p,_(DQ1R){slash}(DQ3R){slash}(DQ1R)-PadM19)") (class "Default")
      (node (ref "U56") (pin "M19") (pinfunction "IO,_DIFFIO_R21p,_(DQ1R)/(DQ3R)/(DQ1R)_M19") (pintype "bidirectional"))
    )
    (net (code "234") (name "unconnected-(U56E-IO,_DIFFIO_R24p,_(DQS1R{slash}CQ1R#,DPCLK6){slash}(DQS1R{slash}CQ1R#,DPCLK6){slash}(DQS1R{slash}CQ1R#,DPCLK6)-PadN18)") (class "Default")
      (node (ref "U56") (pin "N18") (pinfunction "IO,_DIFFIO_R24p,_(DQS1R/CQ1R#,DPCLK6)/(DQS1R/CQ1R#,DPCLK6)/(DQS1R/CQ1R#,DPCLK6)_N18") (pintype "bidirectional"))
    )
    (net (code "235") (name "unconnected-(U56E-IO,_DIFFIO_R25n,_(DQ1R){slash}(DQ3R){slash}(DQ1R)-PadN20)") (class "Default")
      (node (ref "U56") (pin "N20") (pinfunction "IO,_DIFFIO_R25n,_(DQ1R)/(DQ3R)/(DQ1R)_N20") (pintype "bidirectional"))
    )
    (net (code "236") (name "unconnected-(U56E-IO,_DIFFIO_R29n,_(DQ1R){slash}(DQ3R){slash}(DQ1R)-PadR22)") (class "Default")
      (node (ref "U56") (pin "R22") (pinfunction "IO,_DIFFIO_R29n,_(DQ1R)/(DQ3R)/(DQ1R)_R22") (pintype "bidirectional"))
    )
    (net (code "237") (name "unconnected-(U56E-IO,_DIFFIO_R31n-PadR18)") (class "Default")
      (node (ref "U56") (pin "R18") (pinfunction "IO,_DIFFIO_R31n_R18") (pintype "bidirectional"))
    )
    (net (code "238") (name "unconnected-(U56E-IO,_DIFFIO_R31p,_(DM1R{slash}BWS#1R){slash}(DM3R{slash}BWS#3R){slash}(DM1R{slash}BWS#1R)-PadR19)") (class "Default")
      (node (ref "U56") (pin "R19") (pinfunction "IO,_DIFFIO_R31p,_(DM1R/BWS#1R)/(DM3R/BWS#3R)/(DM1R/BWS#1R)_R19") (pintype "bidirectional"))
    )
    (net (code "239") (name "unconnected-(U56E-IO,_DIFFIO_R32n,_(DQ3R){slash}(DQ3R){slash}(DQ1R)-PadU22)") (class "Default")
      (node (ref "U56") (pin "U22") (pinfunction "IO,_DIFFIO_R32n,_(DQ3R)/(DQ3R)/(DQ1R)_U22") (pintype "bidirectional"))
    )
    (net (code "240") (name "unconnected-(U56E-IO,_DIFFIO_R32p,_(DQ3R){slash}(DQ3R){slash}(DQ1R)-PadU21)") (class "Default")
      (node (ref "U56") (pin "U21") (pinfunction "IO,_DIFFIO_R32p,_(DQ3R)/(DQ3R)/(DQ1R)_U21") (pintype "bidirectional"))
    )
    (net (code "241") (name "unconnected-(U56E-IO,_DIFFIO_R33n,_(DQ3R){slash}(DQ3R){slash}(DQ1R)-PadR20)") (class "Default")
      (node (ref "U56") (pin "R20") (pinfunction "IO,_DIFFIO_R33n,_(DQ3R)/(DQ3R)/(DQ1R)_R20") (pintype "bidirectional"))
    )
    (net (code "242") (name "unconnected-(U56E-IO,_RDN3-PadT18)") (class "Default")
      (node (ref "U56") (pin "T18") (pinfunction "IO,_RDN3_T18") (pintype "bidirectional"))
    )
    (net (code "243") (name "unconnected-(U56E-IO,_RUP3-PadT17)") (class "Default")
      (node (ref "U56") (pin "T17") (pinfunction "IO,_RUP3_T17") (pintype "bidirectional"))
    )
    (net (code "244") (name "unconnected-(U56E-IO,_VREFB5N0-PadN19)") (class "Default")
      (node (ref "U56") (pin "N19") (pinfunction "IO,_VREFB5N0_N19") (pintype "bidirectional"))
    )
    (net (code "245") (name "unconnected-(U56E-IO,_VREFB5N1-PadP20)") (class "Default")
      (node (ref "U56") (pin "P20") (pinfunction "IO,_VREFB5N1_P20") (pintype "bidirectional"))
    )
    (net (code "246") (name "unconnected-(U56E-IO,_VREFB5N2-PadW19)") (class "Default")
      (node (ref "U56") (pin "W19") (pinfunction "IO,_VREFB5N2_W19") (pintype "bidirectional"))
    )
    (net (code "247") (name "unconnected-(U56E-IO-PadM16)") (class "Default")
      (node (ref "U56") (pin "M16") (pinfunction "IO_M16") (pintype "bidirectional"))
    )
    (net (code "248") (name "unconnected-(U56F-IO,_DIFFIO_R1n,_(DQ2R){slash}(DQ1R){slash}(DQ1R)-PadF17)") (class "Default")
      (node (ref "U56") (pin "F17") (pinfunction "IO,_DIFFIO_R1n,_(DQ2R)/(DQ1R)/(DQ1R)_F17") (pintype "bidirectional"))
    )
    (net (code "249") (name "unconnected-(U56F-IO,_DIFFIO_R4n,_(PADD20),_(DQS2R{slash}CQ3R,CDPCLK5){slash}(DQS2R{slash}CQ3R,CDPCLK5){slash}(DQS2R{slash}CQ3R,CDPCLK5)-PadC20)") (class "Default")
      (node (ref "U56") (pin "C20") (pinfunction "IO,_DIFFIO_R4n,_(PADD20),_(DQS2R/CQ3R,CDPCLK5)/(DQS2R/CQ3R,CDPCLK5)/(DQS2R/CQ3R,CDPCLK5)_C20") (pintype "bidirectional"))
    )
    (net (code "250") (name "unconnected-(U56F-IO,_DIFFIO_R8n,_(PADD23),_(DQ2R){slash}(DQ1R){slash}(DQ1R)-PadG18)") (class "Default")
      (node (ref "U56") (pin "G18") (pinfunction "IO,_DIFFIO_R8n,_(PADD23),_(DQ2R)/(DQ1R)/(DQ1R)_G18") (pintype "bidirectional"))
    )
    (net (code "251") (name "unconnected-(U56F-IO,_DIFFIO_R8p-PadH17)") (class "Default")
      (node (ref "U56") (pin "H17") (pinfunction "IO,_DIFFIO_R8p_H17") (pintype "bidirectional"))
    )
    (net (code "252") (name "unconnected-(U56F-IO,_DIFFIO_R9p,_(DQ2R){slash}(DQ1R){slash}(DQ1R)-PadF19)") (class "Default")
      (node (ref "U56") (pin "F19") (pinfunction "IO,_DIFFIO_R9p,_(DQ2R)/(DQ1R)/(DQ1R)_F19") (pintype "bidirectional"))
    )
    (net (code "253") (name "unconnected-(U56F-IO,_DIFFIO_R12n,_(DQ0R){slash}(DQ1R){slash}(DQ1R)-PadH20)") (class "Default")
      (node (ref "U56") (pin "H20") (pinfunction "IO,_DIFFIO_R12n,_(DQ0R)/(DQ1R)/(DQ1R)_H20") (pintype "bidirectional"))
    )
    (net (code "254") (name "unconnected-(U56F-IO,_DIFFIO_R12p,_(DQ0R){slash}(DQ1R){slash}(DQ1R)-PadH19)") (class "Default")
      (node (ref "U56") (pin "H19") (pinfunction "IO,_DIFFIO_R12p,_(DQ0R)/(DQ1R)/(DQ1R)_H19") (pintype "bidirectional"))
    )
    (net (code "255") (name "unconnected-(U56F-IO,_DIFFIO_R13n-PadJ20)") (class "Default")
      (node (ref "U56") (pin "J20") (pinfunction "IO,_DIFFIO_R13n_J20") (pintype "bidirectional"))
    )
    (net (code "256") (name "unconnected-(U56F-IO,_DIFFIO_R13p-PadJ19)") (class "Default")
      (node (ref "U56") (pin "J19") (pinfunction "IO,_DIFFIO_R13p_J19") (pintype "bidirectional"))
    )
    (net (code "257") (name "unconnected-(U56F-IO,_DIFFIO_R14n,_(DQ0R){slash}(DQ1R){slash}(DQ1R)-PadF22)") (class "Default")
      (node (ref "U56") (pin "F22") (pinfunction "IO,_DIFFIO_R14n,_(DQ0R)/(DQ1R)/(DQ1R)_F22") (pintype "bidirectional"))
    )
    (net (code "258") (name "unconnected-(U56F-IO,_DIFFIO_R14p,_(DQ0R){slash}(DQ1R){slash}(DQ1R)-PadF21)") (class "Default")
      (node (ref "U56") (pin "F21") (pinfunction "IO,_DIFFIO_R14p,_(DQ0R)/(DQ1R)/(DQ1R)_F21") (pintype "bidirectional"))
    )
    (net (code "259") (name "unconnected-(U56F-IO,_DIFFIO_R16n,_(DQ0R){slash}(DQ1R){slash}(DQ1R)-PadK18)") (class "Default")
      (node (ref "U56") (pin "K18") (pinfunction "IO,_DIFFIO_R16n,_(DQ0R)/(DQ1R)/(DQ1R)_K18") (pintype "bidirectional"))
    )
    (net (code "260") (name "unconnected-(U56F-IO,_DIFFIO_R16p-PadJ18)") (class "Default")
      (node (ref "U56") (pin "J18") (pinfunction "IO,_DIFFIO_R16p_J18") (pintype "bidirectional"))
    )
    (net (code "261") (name "unconnected-(U56F-IO,_DIFFIO_R17n,_(DQ0R){slash}(DQ1R){slash}(DQ1R)-PadH22)") (class "Default")
      (node (ref "U56") (pin "H22") (pinfunction "IO,_DIFFIO_R17n,_(DQ0R)/(DQ1R)/(DQ1R)_H22") (pintype "bidirectional"))
    )
    (net (code "262") (name "unconnected-(U56F-IO,_DIFFIO_R17p,_(DQ0R){slash}(DQ1R){slash}(DQ1R)-PadH21)") (class "Default")
      (node (ref "U56") (pin "H21") (pinfunction "IO,_DIFFIO_R17p,_(DQ0R)/(DQ1R)/(DQ1R)_H21") (pintype "bidirectional"))
    )
    (net (code "263") (name "unconnected-(U56F-IO,_DIFFIO_R18n,_(DQS0R{slash}CQ1R,DPCLK7){slash}(DQS0R{slash}CQ1R,DPCLK7){slash}(DQS0R{slash}CQ1R,DPCLK7)-PadJ22)") (class "Default")
      (node (ref "U56") (pin "J22") (pinfunction "IO,_DIFFIO_R18n,_(DQS0R/CQ1R,DPCLK7)/(DQS0R/CQ1R,DPCLK7)/(DQS0R/CQ1R,DPCLK7)_J22") (pintype "bidirectional"))
    )
    (net (code "264") (name "unconnected-(U56F-IO,_DIFFIO_R18p,_(DM0R){slash}(DM1R{slash}BWS#1R){slash}(DM1R{slash}BWS#1R)-PadJ21)") (class "Default")
      (node (ref "U56") (pin "J21") (pinfunction "IO,_DIFFIO_R18p,_(DM0R)/(DM1R/BWS#1R)/(DM1R/BWS#1R)_J21") (pintype "bidirectional"))
    )
    (net (code "265") (name "unconnected-(U56F-IO,_DIFFIO_R19p,_(CLKUSR)-PadK21)") (class "Default")
      (node (ref "U56") (pin "K21") (pinfunction "IO,_DIFFIO_R19p,_(CLKUSR)_K21") (pintype "bidirectional"))
    )
    (net (code "266") (name "unconnected-(U56F-IO,_VREFB6N0-PadD20)") (class "Default")
      (node (ref "U56") (pin "D20") (pinfunction "IO,_VREFB6N0_D20") (pintype "bidirectional"))
    )
    (net (code "267") (name "unconnected-(U56F-IO,_VREFB6N1-PadH18)") (class "Default")
      (node (ref "U56") (pin "H18") (pinfunction "IO,_VREFB6N1_H18") (pintype "bidirectional"))
    )
    (net (code "268") (name "unconnected-(U56F-IO,_VREFB6N2-PadK19)") (class "Default")
      (node (ref "U56") (pin "K19") (pinfunction "IO,_VREFB6N2_K19") (pintype "bidirectional"))
    )
    (net (code "269") (name "unconnected-(U56G-IO,_(_){slash}(DQ5T){slash}(DQ5T)-PadE12)") (class "Default")
      (node (ref "U56") (pin "E12") (pinfunction "IO,_(_)/(DQ5T)/(DQ5T)_E12") (pintype "bidirectional"))
    )
    (net (code "270") (name "unconnected-(U56G-IO,_DIFFIO_T25n,_(PADD13)-PadE11)") (class "Default")
      (node (ref "U56") (pin "E11") (pinfunction "IO,_DIFFIO_T25n,_(PADD13)_E11") (pintype "bidirectional"))
    )
    (net (code "271") (name "unconnected-(U56G-IO,_DIFFIO_T25p,_(PADD14),_(DM4T){slash}(DM5T{slash}BWS#5T){slash}(DM5T{slash}BWS#5T)-PadF11)") (class "Default")
      (node (ref "U56") (pin "F11") (pinfunction "IO,_DIFFIO_T25p,_(PADD14),_(DM4T)/(DM5T/BWS#5T)/(DM5T/BWS#5T)_F11") (pintype "bidirectional"))
    )
    (net (code "272") (name "unconnected-(U56G-IO,_DIFFIO_T27n,_(PADD9),_(DQ4T){slash}(DQ5T){slash}(DQ5T)-PadA14)") (class "Default")
      (node (ref "U56") (pin "A14") (pinfunction "IO,_DIFFIO_T27n,_(PADD9),_(DQ4T)/(DQ5T)/(DQ5T)_A14") (pintype "bidirectional"))
    )
    (net (code "273") (name "unconnected-(U56G-IO,_DIFFIO_T31n,_(PADD7)-PadC13)") (class "Default")
      (node (ref "U56") (pin "C13") (pinfunction "IO,_DIFFIO_T31n,_(PADD7)_C13") (pintype "bidirectional"))
    )
    (net (code "274") (name "unconnected-(U56G-IO,_DIFFIO_T31p,_(PADD8),_(DQ4T){slash}(DQ5T){slash}(DQ5T)-PadD13)") (class "Default")
      (node (ref "U56") (pin "D13") (pinfunction "IO,_DIFFIO_T31p,_(PADD8),_(DQ4T)/(DQ5T)/(DQ5T)_D13") (pintype "bidirectional"))
    )
    (net (code "275") (name "unconnected-(U56G-IO,_DIFFIO_T32p,_(PADD6),_(DQ4T){slash}(DQ5T){slash}(DQ5T)-PadB15)") (class "Default")
      (node (ref "U56") (pin "B15") (pinfunction "IO,_DIFFIO_T32p,_(PADD6),_(DQ4T)/(DQ5T)/(DQ5T)_B15") (pintype "bidirectional"))
    )
    (net (code "276") (name "unconnected-(U56G-IO,_DIFFIO_T33n,_(PADD3),_(DQ4T){slash}(DQ5T){slash}(DQ5T)-PadE14)") (class "Default")
      (node (ref "U56") (pin "E14") (pinfunction "IO,_DIFFIO_T33n,_(PADD3),_(DQ4T)/(DQ5T)/(DQ5T)_E14") (pintype "bidirectional"))
    )
    (net (code "277") (name "unconnected-(U56G-IO,_DIFFIO_T33p,_(PADD4),_(DQS2T{slash}CQ3T,DPCLK8){slash}(DQS2T{slash}CQ3T,DPCLK8){slash}(DQS2T{slash}CQ3T,DPCLK8)-PadF13)") (class "Default")
      (node (ref "U56") (pin "F13") (pinfunction "IO,_DIFFIO_T33p,_(PADD4),_(DQS2T/CQ3T,DPCLK8)/(DQS2T/CQ3T,DPCLK8)/(DQS2T/CQ3T,DPCLK8)_F13") (pintype "bidirectional"))
    )
    (net (code "278") (name "unconnected-(U56G-IO,_DIFFIO_T38n-PadD15)") (class "Default")
      (node (ref "U56") (pin "D15") (pinfunction "IO,_DIFFIO_T38n_D15") (pintype "bidirectional"))
    )
    (net (code "279") (name "unconnected-(U56G-IO,_DIFFIO_T38p,_(DQ2T){slash}(DQ5T){slash}(DQ5T)-PadE15)") (class "Default")
      (node (ref "U56") (pin "E15") (pinfunction "IO,_DIFFIO_T38p,_(DQ2T)/(DQ5T)/(DQ5T)_E15") (pintype "bidirectional"))
    )
    (net (code "280") (name "unconnected-(U56G-IO,_DIFFIO_T40p,_(DQ2T){slash}(DQ5T){slash}(DQ5T)-PadC17)") (class "Default")
      (node (ref "U56") (pin "C17") (pinfunction "IO,_DIFFIO_T40p,_(DQ2T)/(DQ5T)/(DQ5T)_C17") (pintype "bidirectional"))
    )
    (net (code "281") (name "unconnected-(U56G-IO,_DIFFIO_T42p,_(DQ2T){slash}(DQ5T){slash}(DQ5T)-PadD19)") (class "Default")
      (node (ref "U56") (pin "D19") (pinfunction "IO,_DIFFIO_T42p,_(DQ2T)/(DQ5T)/(DQ5T)_D19") (pintype "bidirectional"))
    )
    (net (code "282") (name "unconnected-(U56G-IO,_DIFFIO_T44n-PadC18)") (class "Default")
      (node (ref "U56") (pin "C18") (pinfunction "IO,_DIFFIO_T44n_C18") (pintype "bidirectional"))
    )
    (net (code "283") (name "unconnected-(U56G-IO,_DIFFIO_T44p-PadD18)") (class "Default")
      (node (ref "U56") (pin "D18") (pinfunction "IO,_DIFFIO_T44p_D18") (pintype "bidirectional"))
    )
    (net (code "284") (name "unconnected-(U56G-IO,_DIFFIO_T45p,_(DQS0T{slash}CQ1T,CDPCLK6){slash}(DQS0T{slash}CQ1T,CDPCLK6){slash}(DQS0T{slash}CQ1T,CDPCLK6)-PadF14)") (class "Default")
      (node (ref "U56") (pin "F14") (pinfunction "IO,_DIFFIO_T45p,_(DQS0T/CQ1T,CDPCLK6)/(DQS0T/CQ1T,CDPCLK6)/(DQS0T/CQ1T,CDPCLK6)_F14") (pintype "bidirectional"))
    )
    (net (code "285") (name "unconnected-(U56G-IO,_DIFFIO_T46n,_(DQ2T){slash}(DQ5T){slash}(DQ5T)-PadE16)") (class "Default")
      (node (ref "U56") (pin "E16") (pinfunction "IO,_DIFFIO_T46n,_(DQ2T)/(DQ5T)/(DQ5T)_E16") (pintype "bidirectional"))
    )
    (net (code "286") (name "unconnected-(U56G-IO,_DIFFIO_T46p,_(DQ2T){slash}(DQ5T){slash}(DQ5T)-PadF15)") (class "Default")
      (node (ref "U56") (pin "F15") (pinfunction "IO,_DIFFIO_T46p,_(DQ2T)/(DQ5T)/(DQ5T)_F15") (pintype "bidirectional"))
    )
    (net (code "287") (name "unconnected-(U56G-IO,_VREFB7N0-PadD17)") (class "Default")
      (node (ref "U56") (pin "D17") (pinfunction "IO,_VREFB7N0_D17") (pintype "bidirectional"))
    )
    (net (code "288") (name "unconnected-(U56G-IO,_VREFB7N1-PadC15)") (class "Default")
      (node (ref "U56") (pin "C15") (pinfunction "IO,_VREFB7N1_C15") (pintype "bidirectional"))
    )
    (net (code "289") (name "unconnected-(U56G-IO,_VREFB7N2-PadE13)") (class "Default")
      (node (ref "U56") (pin "E13") (pinfunction "IO,_VREFB7N2_E13") (pintype "bidirectional"))
    )
    (net (code "290") (name "unconnected-(U56H-IO,_DIFFIO_T2n,_(DM3T{slash}BWS#3T){slash}(DM3T{slash}BWS#3T){slash}(DM5T{slash}BWS#5T)-PadF7)") (class "Default")
      (node (ref "U56") (pin "F7") (pinfunction "IO,_DIFFIO_T2n,_(DM3T/BWS#3T)/(DM3T/BWS#3T)/(DM5T/BWS#5T)_F7") (pintype "bidirectional"))
    )
    (net (code "291") (name "unconnected-(U56H-IO,_DIFFIO_T2p-PadG7)") (class "Default")
      (node (ref "U56") (pin "G7") (pinfunction "IO,_DIFFIO_T2p_G7") (pintype "bidirectional"))
    )
    (net (code "292") (name "unconnected-(U56H-IO,_DIFFIO_T3n,_(DQ3T){slash}(DQ3T){slash}(DQ5T)-PadC3)") (class "Default")
      (node (ref "U56") (pin "C3") (pinfunction "IO,_DIFFIO_T3n,_(DQ3T)/(DQ3T)/(DQ5T)_C3") (pintype "bidirectional"))
    )
    (net (code "293") (name "unconnected-(U56H-IO,_DIFFIO_T3p,_(DATA12),_(DQS1T{slash}CQ1T#,CDPCLK7){slash}(DQS1T{slash}CQ1T#,CDPCLK7){slash}(DQS1T{slash}CQ1T#,CDPCLK7)-PadC4)") (class "Default")
      (node (ref "U56") (pin "C4") (pinfunction "IO,_DIFFIO_T3p,_(DATA12),_(DQS1T/CQ1T#,CDPCLK7)/(DQS1T/CQ1T#,CDPCLK7)/(DQS1T/CQ1T#,CDPCLK7)_C4") (pintype "bidirectional"))
    )
    (net (code "294") (name "unconnected-(U56H-IO,_DIFFIO_T6n-PadE7)") (class "Default")
      (node (ref "U56") (pin "E7") (pinfunction "IO,_DIFFIO_T6n_E7") (pintype "bidirectional"))
    )
    (net (code "295") (name "unconnected-(U56H-IO,_DIFFIO_T7p,_(DATA11),_(DQ3T){slash}(DQ3T){slash}(DQ5T)-PadB3)") (class "Default")
      (node (ref "U56") (pin "B3") (pinfunction "IO,_DIFFIO_T7p,_(DATA11),_(DQ3T)/(DQ3T)/(DQ5T)_B3") (pintype "bidirectional"))
    )
    (net (code "296") (name "unconnected-(U56H-IO,_DIFFIO_T9n,_(DATA9),_(DQ3T){slash}(DQ3T){slash}(DQ5T)-PadF8)") (class "Default")
      (node (ref "U56") (pin "F8") (pinfunction "IO,_DIFFIO_T9n,_(DATA9),_(DQ3T)/(DQ3T)/(DQ5T)_F8") (pintype "bidirectional"))
    )
    (net (code "297") (name "unconnected-(U56H-IO,_DIFFIO_T11n,_(DATA7),_(DQ3T){slash}(DQ3T){slash}(DQ5T)-PadC6)") (class "Default")
      (node (ref "U56") (pin "C6") (pinfunction "IO,_DIFFIO_T11n,_(DATA7),_(DQ3T)/(DQ3T)/(DQ5T)_C6") (pintype "bidirectional"))
    )
    (net (code "298") (name "unconnected-(U56H-IO,_DIFFIO_T11p-PadD7)") (class "Default")
      (node (ref "U56") (pin "D7") (pinfunction "IO,_DIFFIO_T11p_D7") (pintype "bidirectional"))
    )
    (net (code "299") (name "unconnected-(U56H-IO,_DIFFIO_T12p,_(DATA6),_(DQ3T){slash}(DQ3T){slash}(DQ5T)-PadF10)") (class "Default")
      (node (ref "U56") (pin "F10") (pinfunction "IO,_DIFFIO_T12p,_(DATA6),_(DQ3T)/(DQ3T)/(DQ5T)_F10") (pintype "bidirectional"))
    )
    (net (code "300") (name "unconnected-(U56H-IO,_DIFFIO_T14n-PadD8)") (class "Default")
      (node (ref "U56") (pin "D8") (pinfunction "IO,_DIFFIO_T14n_D8") (pintype "bidirectional"))
    )
    (net (code "301") (name "unconnected-(U56H-IO,_DIFFIO_T14p-PadE8)") (class "Default")
      (node (ref "U56") (pin "E8") (pinfunction "IO,_DIFFIO_T14p_E8") (pintype "bidirectional"))
    )
    (net (code "302") (name "unconnected-(U56H-IO,_DIFFIO_T15n,_(DATA14),_(DQS3T{slash}CQ3T#,DPCLK11){slash}(DQS3T{slash}CQ3T#,DPCLK11){slash}(DQS3T{slash}CQ3T#,DPCLK11)-PadC8)") (class "Default")
      (node (ref "U56") (pin "C8") (pinfunction "IO,_DIFFIO_T15n,_(DATA14),_(DQS3T/CQ3T#,DPCLK11)/(DQS3T/CQ3T#,DPCLK11)/(DQS3T/CQ3T#,DPCLK11)_C8") (pintype "bidirectional"))
    )
    (net (code "303") (name "unconnected-(U56H-IO,_DIFFIO_T15p,_(DATA13),_(DM5T{slash}BWS#5T){slash}(DM3T{slash}BWS#3T){slash}(DM5T{slash}BWS#5T)-PadC7)") (class "Default")
      (node (ref "U56") (pin "C7") (pinfunction "IO,_DIFFIO_T15p,_(DATA13),_(DM5T/BWS#5T)/(DM3T/BWS#3T)/(DM5T/BWS#5T)_C7") (pintype "bidirectional"))
    )
    (net (code "304") (name "unconnected-(U56H-IO,_DIFFIO_T16n-PadE9)") (class "Default")
      (node (ref "U56") (pin "E9") (pinfunction "IO,_DIFFIO_T16n_E9") (pintype "bidirectional"))
    )
    (net (code "305") (name "unconnected-(U56H-IO,_DIFFIO_T17p,_(DATA15),_(DQ5T){slash}(DQ3T){slash}(DQ5T)-PadB6)") (class "Default")
      (node (ref "U56") (pin "B6") (pinfunction "IO,_DIFFIO_T17p,_(DATA15),_(DQ5T)/(DQ3T)/(DQ5T)_B6") (pintype "bidirectional"))
    )
    (net (code "306") (name "unconnected-(U56H-IO,_DIFFIO_T18p,_(DATA4),_(DQ5T){slash}(DQ3T){slash}(DQ5T)-PadB7)") (class "Default")
      (node (ref "U56") (pin "B7") (pinfunction "IO,_DIFFIO_T18p,_(DATA4),_(DQ5T)/(DQ3T)/(DQ5T)_B7") (pintype "bidirectional"))
    )
    (net (code "307") (name "unconnected-(U56H-IO,_DIFFIO_T24n,_(DQ5T){slash}(DQ3T){slash}(DQ5T)-PadD10)") (class "Default")
      (node (ref "U56") (pin "D10") (pinfunction "IO,_DIFFIO_T24n,_(DQ5T)/(DQ3T)/(DQ5T)_D10") (pintype "bidirectional"))
    )
    (net (code "308") (name "unconnected-(U56H-IO,_PLL3_CLKOUTn-PadE6)") (class "Default")
      (node (ref "U56") (pin "E6") (pinfunction "IO,_PLL3_CLKOUTn_E6") (pintype "bidirectional"))
    )
    (net (code "309") (name "unconnected-(U56H-IO,_PLL3_CLKOUTp-PadE5)") (class "Default")
      (node (ref "U56") (pin "E5") (pinfunction "IO,_PLL3_CLKOUTp_E5") (pintype "bidirectional"))
    )
    (net (code "310") (name "unconnected-(U56H-IO,_VREFB8N0-PadC10)") (class "Default")
      (node (ref "U56") (pin "C10") (pinfunction "IO,_VREFB8N0_C10") (pintype "bidirectional"))
    )
    (net (code "311") (name "unconnected-(U56H-IO,_VREFB8N1-PadB5)") (class "Default")
      (node (ref "U56") (pin "B5") (pinfunction "IO,_VREFB8N1_B5") (pintype "bidirectional"))
    )
    (net (code "312") (name "unconnected-(U56H-IO,_VREFB8N2-PadD6)") (class "Default")
      (node (ref "U56") (pin "D6") (pinfunction "IO,_VREFB8N2_D6") (pintype "bidirectional"))
    )
    (net (code "313") (name "unconnected-(U56H-IO-PadF9)") (class "Default")
      (node (ref "U56") (pin "F9") (pinfunction "IO_F9") (pintype "bidirectional"))
    )
    (net (code "314") (name "unconnected-(U56I-CLK1,_DIFFCLK_0n-PadG1)") (class "Default")
      (node (ref "U56") (pin "G1") (pinfunction "CLK1,_DIFFCLK_0n_G1") (pintype "input"))
    )
    (net (code "315") (name "unconnected-(U56I-CLK2,_DIFFCLK_1p-PadT2)") (class "Default")
      (node (ref "U56") (pin "T2") (pinfunction "CLK2,_DIFFCLK_1p_T2") (pintype "input"))
    )
    (net (code "316") (name "unconnected-(U56I-CLK3,_DIFFCLK_1n-PadT1)") (class "Default")
      (node (ref "U56") (pin "T1") (pinfunction "CLK3,_DIFFCLK_1n_T1") (pintype "input"))
    )
    (net (code "317") (name "unconnected-(U56I-CLK4,_DIFFCLK_2p-PadG21)") (class "Default")
      (node (ref "U56") (pin "G21") (pinfunction "CLK4,_DIFFCLK_2p_G21") (pintype "input"))
    )
    (net (code "318") (name "unconnected-(U56I-CLK7,_DIFFCLK_3n-PadT22)") (class "Default")
      (node (ref "U56") (pin "T22") (pinfunction "CLK7,_DIFFCLK_3n_T22") (pintype "input"))
    )
    (net (code "319") (name "unconnected-(U56I-CLK8,_DIFFCLK_5n-PadA12)") (class "Default")
      (node (ref "U56") (pin "A12") (pinfunction "CLK8,_DIFFCLK_5n_A12") (pintype "input"))
    )
    (net (code "320") (name "unconnected-(U56I-CLK9,_DIFFCLK_5p-PadB12)") (class "Default")
      (node (ref "U56") (pin "B12") (pinfunction "CLK9,_DIFFCLK_5p_B12") (pintype "input"))
    )
    (net (code "321") (name "unconnected-(U56I-CLK11,_DIFFCLK_4p-PadB11)") (class "Default")
      (node (ref "U56") (pin "B11") (pinfunction "CLK11,_DIFFCLK_4p_B11") (pintype "input"))
    )
    (net (code "322") (name "unconnected-(U56I-CLK13,_DIFFCLK_7p-PadAA12)") (class "Default")
      (node (ref "U56") (pin "AA12") (pinfunction "CLK13,_DIFFCLK_7p_AA12") (pintype "input"))
    )
    (net (code "323") (name "unconnected-(U56I-CLK14,_DIFFCLK_6n-PadAB11)") (class "Default")
      (node (ref "U56") (pin "AB11") (pinfunction "CLK14,_DIFFCLK_6n_AB11") (pintype "input"))
    )
    (net (code "324") (name "unconnected-(U56I-CLK15,_DIFFCLK_6p-PadAA11)") (class "Default")
      (node (ref "U56") (pin "AA11") (pinfunction "CLK15,_DIFFCLK_6p_AA11") (pintype "input"))
    )
    (net (code "325") (name "unconnected-(U59-NC-Pad1)") (class "Default")
      (node (ref "U59") (pin "1") (pinfunction "NC_1") (pintype "passive"))
    )
    (net (code "326") (name "unconnected-(U61-Pad3)") (class "Default")
      (node (ref "U61") (pin "3") (pintype "passive"))
    )
    (net (code "327") (name "unconnected-(U61-Pad4)") (class "Default")
      (node (ref "U61") (pin "4") (pintype "passive"))
    )
    (net (code "328") (name "unconnected-(U61-Pad5)") (class "Default")
      (node (ref "U61") (pin "5") (pintype "passive"))
    )
    (net (code "329") (name "unconnected-(U61-Pad6)") (class "Default")
      (node (ref "U61") (pin "6") (pintype "passive"))
    )
    (net (code "330") (name "unconnected-(U61-Pad11)") (class "Default")
      (node (ref "U61") (pin "11") (pintype "passive"))
    )
    (net (code "331") (name "unconnected-(U61-Pad12)") (class "Default")
      (node (ref "U61") (pin "12") (pintype "passive"))
    )
    (net (code "332") (name "unconnected-(U61-Pad13)") (class "Default")
      (node (ref "U61") (pin "13") (pintype "passive"))
    )
    (net (code "333") (name "unconnected-(U61-Pad14)") (class "Default")
      (node (ref "U61") (pin "14") (pintype "passive"))
    )
  )
)
